# Hive_1_5.net
KiCad netlist of a schematic drawn in EAGLE
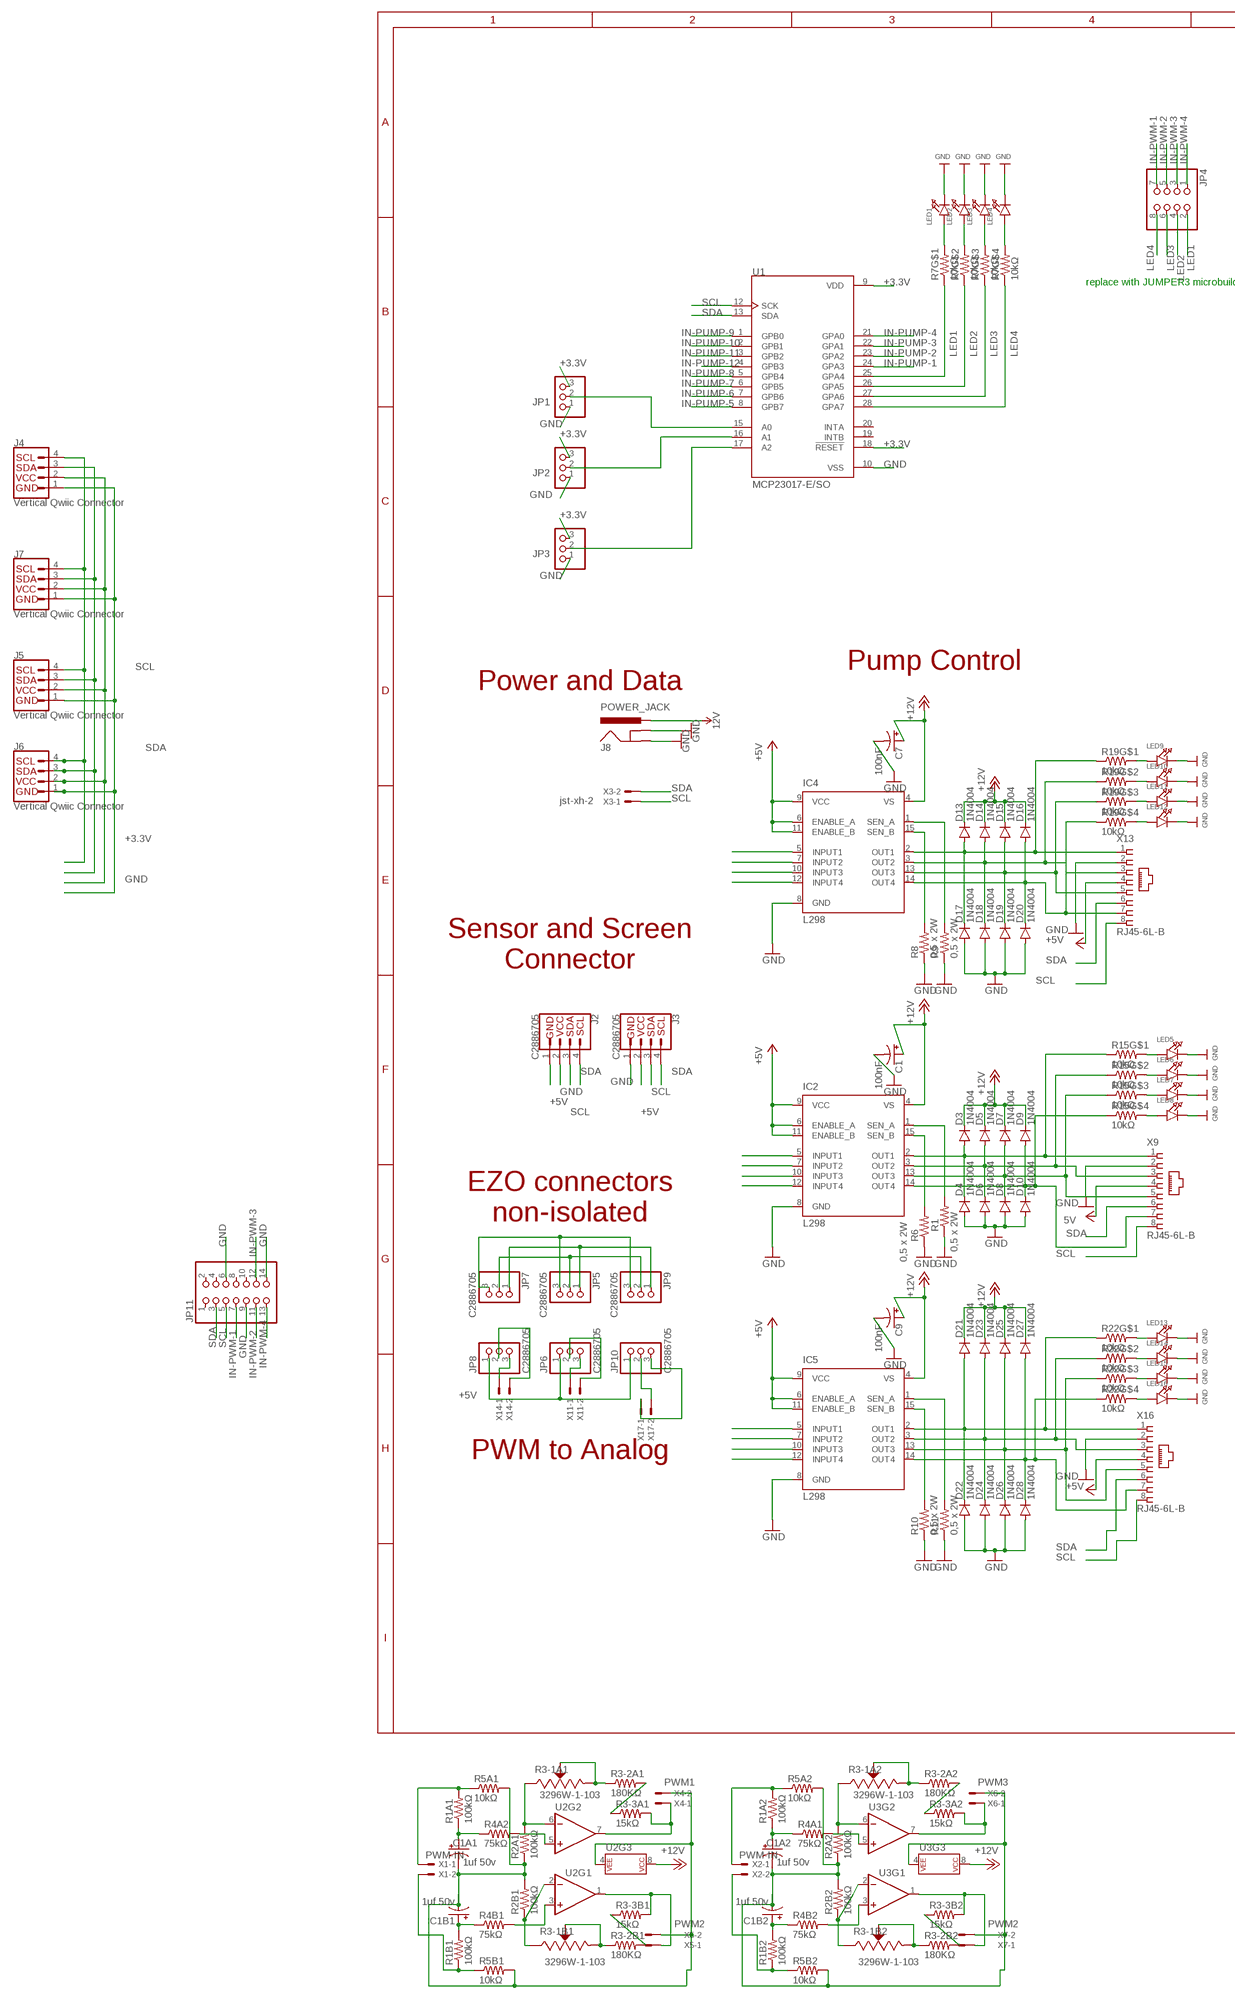
[diagram p0: schematic, sheet 1, part 1 of 2]
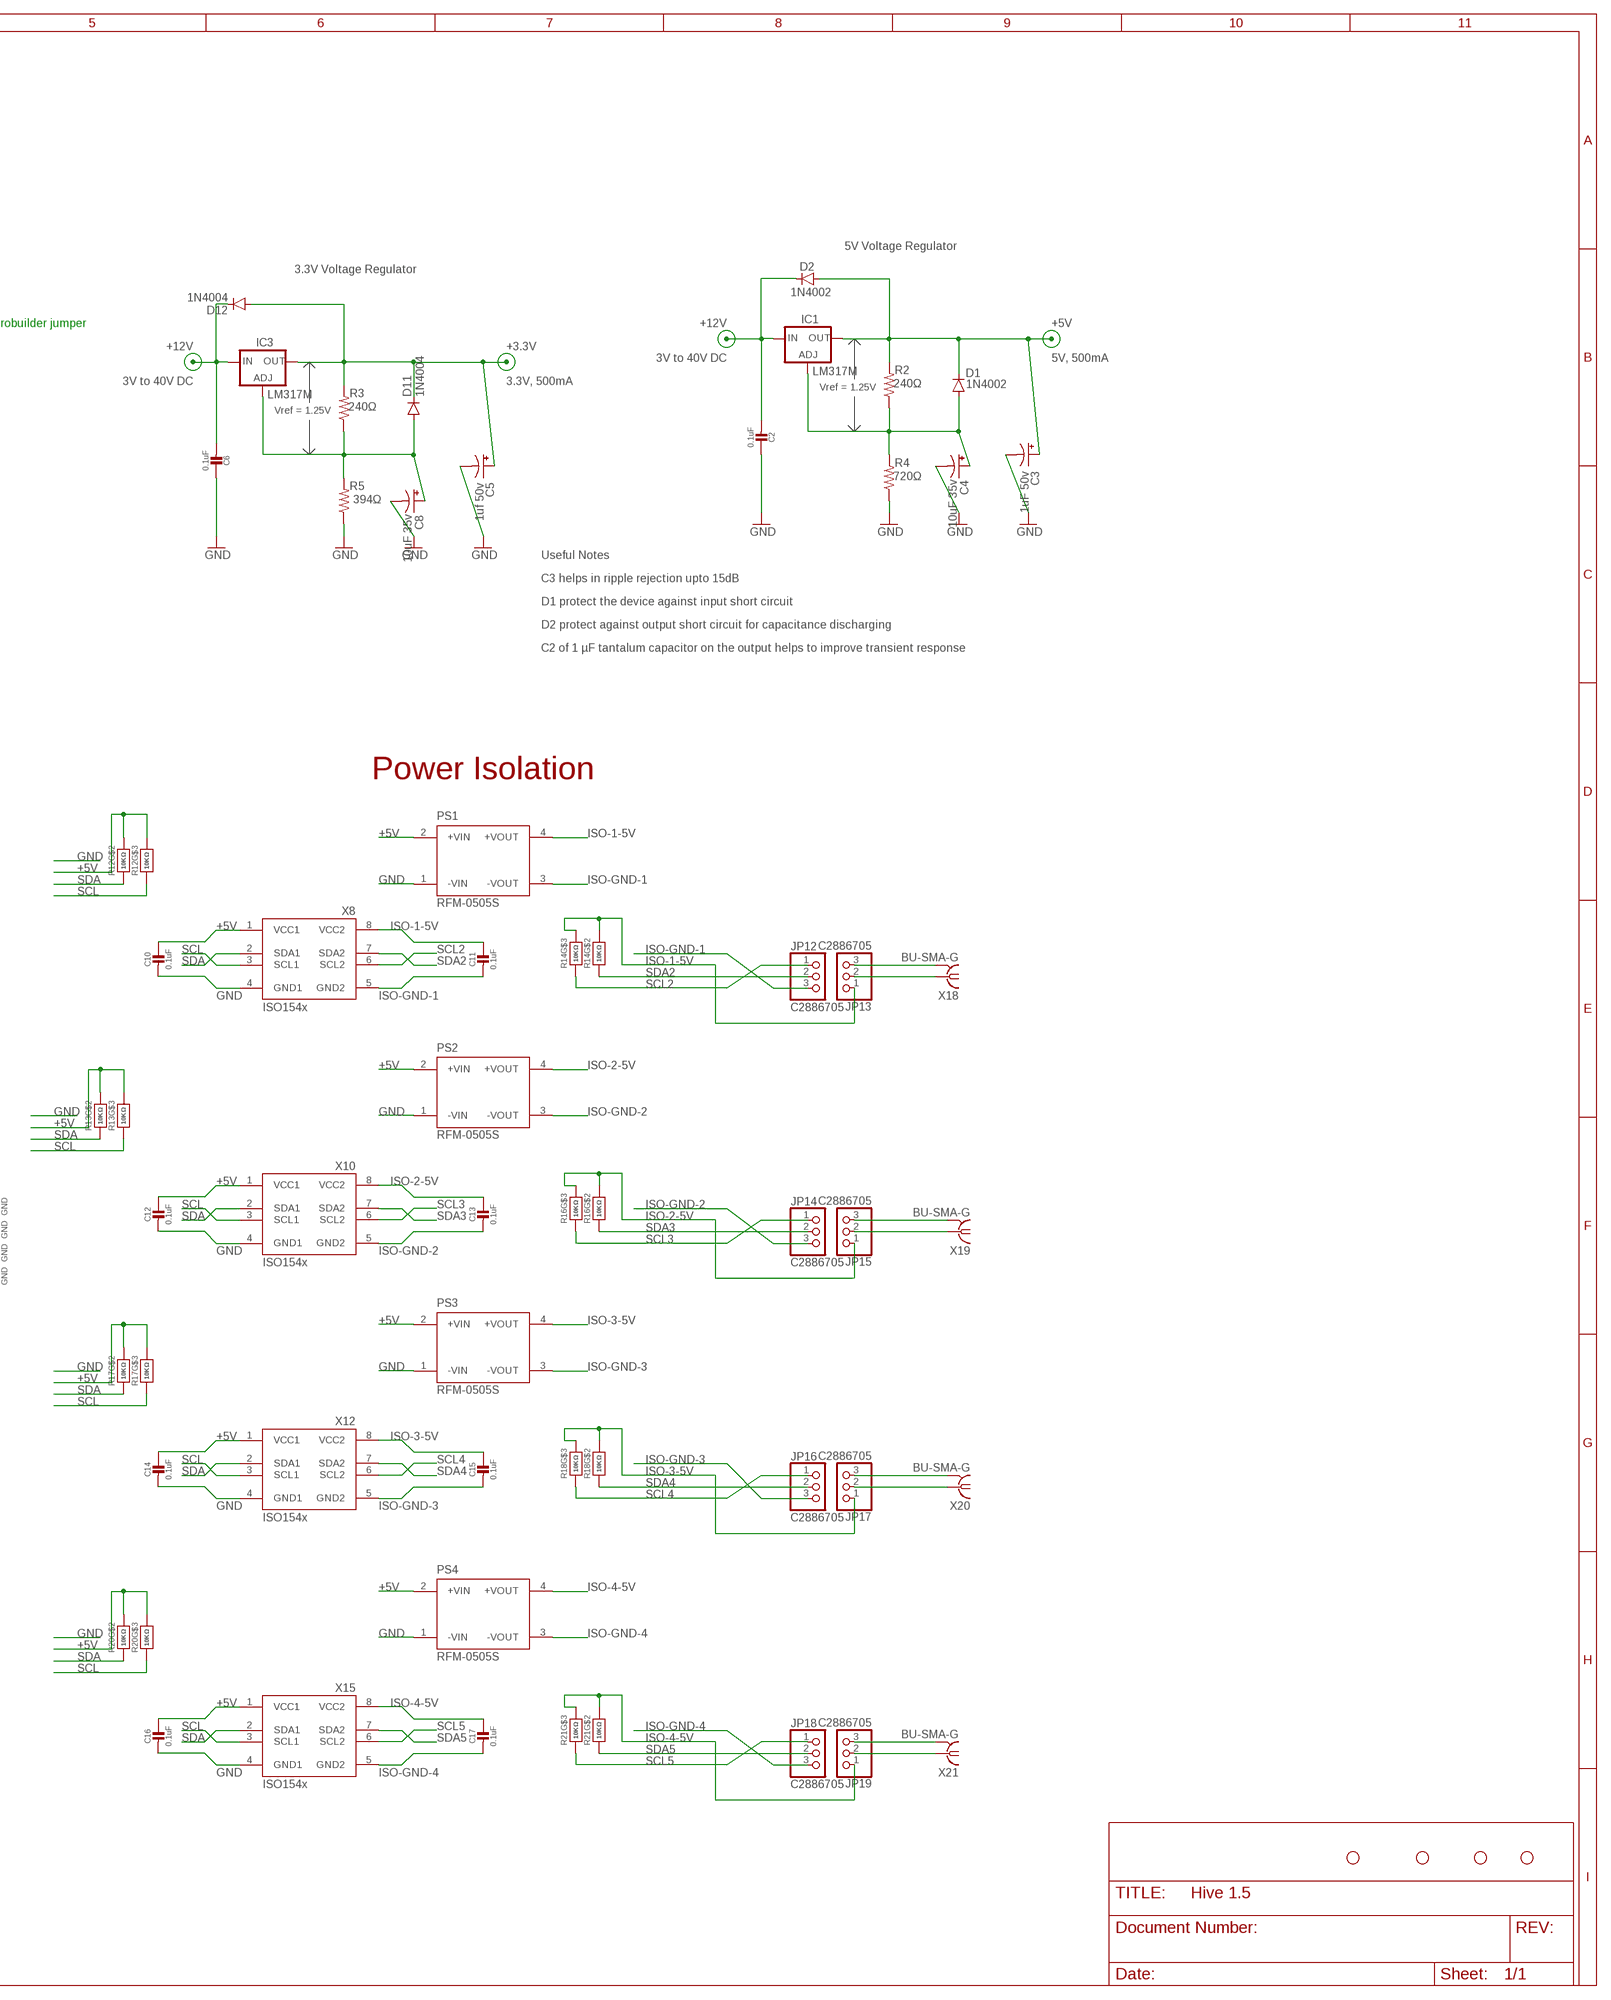
[diagram p1: schematic, sheet 1, part 2 of 2]

(export (version "E")
  (design (tool "Eeschema 10.0.6"))
  (components
    (comp (ref "C1")
      (value "100nF")
      (footprint "eagle-import:UD-4X5,8_NICHICON")
      (libsource (lib "eagle-import") (part "CPOL-USUD-4X5,8"))
    )
    (comp (ref "C1A1")
      (value "1uf 50v")
      (footprint "eagle-import:UD-4X5,8_NICHICON")
      (libsource (lib "eagle-import") (part "CPOL-USUD-4X5,8"))
    )
    (comp (ref "C1A2")
      (value "1uf 50v")
      (footprint "eagle-import:UD-4X5,8_NICHICON")
      (libsource (lib "eagle-import") (part "CPOL-USUD-4X5,8"))
    )
    (comp (ref "C1B1")
      (value "1uf 50v")
      (footprint "eagle-import:UD-4X5,8_NICHICON")
      (libsource (lib "eagle-import") (part "CPOL-USUD-4X5,8"))
    )
    (comp (ref "C1B2")
      (value "1uf 50v")
      (footprint "eagle-import:UD-4X5,8_NICHICON")
      (libsource (lib "eagle-import") (part "CPOL-USUD-4X5,8"))
    )
    (comp (ref "C2")
      (value "0.1uF")
      (footprint "eagle-import:0603-NO")
      (libsource (lib "eagle-import") (part "CAP_CERAMIC0603_NO"))
    )
    (comp (ref "C3")
      (value "1uF 50v")
      (footprint "eagle-import:UD-4X5,8_NICHICON")
      (libsource (lib "eagle-import") (part "CPOL-USUD-4X5,8"))
    )
    (comp (ref "C4")
      (value "10uF 35v")
      (footprint "eagle-import:UD-4X5,8_NICHICON")
      (libsource (lib "eagle-import") (part "CPOL-USUD-4X5,8"))
    )
    (comp (ref "C5")
      (value "1uf 50v")
      (footprint "eagle-import:UD-4X5,8_NICHICON")
      (libsource (lib "eagle-import") (part "CPOL-USUD-4X5,8"))
    )
    (comp (ref "C6")
      (value "0.1uF")
      (footprint "eagle-import:0603-NO")
      (libsource (lib "eagle-import") (part "CAP_CERAMIC0603_NO"))
    )
    (comp (ref "C7")
      (value "100nF")
      (footprint "eagle-import:UD-4X5,8_NICHICON")
      (libsource (lib "eagle-import") (part "CPOL-USUD-4X5,8"))
    )
    (comp (ref "C8")
      (value "10uF 35v")
      (footprint "eagle-import:UD-4X5,8_NICHICON")
      (libsource (lib "eagle-import") (part "CPOL-USUD-4X5,8"))
    )
    (comp (ref "C9")
      (value "100nF")
      (footprint "eagle-import:UD-4X5,8_NICHICON")
      (libsource (lib "eagle-import") (part "CPOL-USUD-4X5,8"))
    )
    (comp (ref "C10")
      (value "0.1uF")
      (footprint "eagle-import:0603-NO")
      (libsource (lib "eagle-import") (part "CAP_CERAMIC0603_NO"))
    )
    (comp (ref "C11")
      (value "0.1uF")
      (footprint "eagle-import:0603-NO")
      (libsource (lib "eagle-import") (part "CAP_CERAMIC0603_NO"))
    )
    (comp (ref "C12")
      (value "0.1uF")
      (footprint "eagle-import:0603-NO")
      (libsource (lib "eagle-import") (part "CAP_CERAMIC0603_NO"))
    )
    (comp (ref "C13")
      (value "0.1uF")
      (footprint "eagle-import:0603-NO")
      (libsource (lib "eagle-import") (part "CAP_CERAMIC0603_NO"))
    )
    (comp (ref "C14")
      (value "0.1uF")
      (footprint "eagle-import:0603-NO")
      (libsource (lib "eagle-import") (part "CAP_CERAMIC0603_NO"))
    )
    (comp (ref "C15")
      (value "0.1uF")
      (footprint "eagle-import:0603-NO")
      (libsource (lib "eagle-import") (part "CAP_CERAMIC0603_NO"))
    )
    (comp (ref "C16")
      (value "0.1uF")
      (footprint "eagle-import:0603-NO")
      (libsource (lib "eagle-import") (part "CAP_CERAMIC0603_NO"))
    )
    (comp (ref "C17")
      (value "0.1uF")
      (footprint "eagle-import:0603-NO")
      (libsource (lib "eagle-import") (part "CAP_CERAMIC0603_NO"))
    )
    (comp (ref "D1")
      (value "1N4002")
      (footprint "eagle-import:DO214BA")
      (libsource (lib "eagle-import") (part "DIODE-DO214BA"))
    )
    (comp (ref "D2")
      (value "1N4002")
      (footprint "eagle-import:DO214BA")
      (libsource (lib "eagle-import") (part "DIODE-DO214BA"))
    )
    (comp (ref "D3")
      (value "1N4004")
      (footprint "eagle-import:DO214BA")
      (libsource (lib "eagle-import") (part "DIODE-DO214BA"))
    )
    (comp (ref "D4")
      (value "1N4004")
      (footprint "eagle-import:DO214BA")
      (libsource (lib "eagle-import") (part "DIODE-DO214BA"))
    )
    (comp (ref "D5")
      (value "1N4004")
      (footprint "eagle-import:DO214BA")
      (libsource (lib "eagle-import") (part "DIODE-DO214BA"))
    )
    (comp (ref "D6")
      (value "1N4004")
      (footprint "eagle-import:DO214BA")
      (libsource (lib "eagle-import") (part "DIODE-DO214BA"))
    )
    (comp (ref "D7")
      (value "1N4004")
      (footprint "eagle-import:DO214BA")
      (libsource (lib "eagle-import") (part "DIODE-DO214BA"))
    )
    (comp (ref "D8")
      (value "1N4004")
      (footprint "eagle-import:DO214BA")
      (libsource (lib "eagle-import") (part "DIODE-DO214BA"))
    )
    (comp (ref "D9")
      (value "1N4004")
      (footprint "eagle-import:DO214BA")
      (libsource (lib "eagle-import") (part "DIODE-DO214BA"))
    )
    (comp (ref "D10")
      (value "1N4004")
      (footprint "eagle-import:DO214BA")
      (libsource (lib "eagle-import") (part "DIODE-DO214BA"))
    )
    (comp (ref "D11")
      (value "1N4004")
      (footprint "eagle-import:DO214BA")
      (libsource (lib "eagle-import") (part "DIODE-DO214BA"))
    )
    (comp (ref "D12")
      (value "1N4004")
      (footprint "eagle-import:DO214BA")
      (libsource (lib "eagle-import") (part "DIODE-DO214BA"))
    )
    (comp (ref "D13")
      (value "1N4004")
      (footprint "eagle-import:DO214BA")
      (libsource (lib "eagle-import") (part "DIODE-DO214BA"))
    )
    (comp (ref "D14")
      (value "1N4004")
      (footprint "eagle-import:DO214BA")
      (libsource (lib "eagle-import") (part "DIODE-DO214BA"))
    )
    (comp (ref "D15")
      (value "1N4004")
      (footprint "eagle-import:DO214BA")
      (libsource (lib "eagle-import") (part "DIODE-DO214BA"))
    )
    (comp (ref "D16")
      (value "1N4004")
      (footprint "eagle-import:DO214BA")
      (libsource (lib "eagle-import") (part "DIODE-DO214BA"))
    )
    (comp (ref "D17")
      (value "1N4004")
      (footprint "eagle-import:DO214BA")
      (libsource (lib "eagle-import") (part "DIODE-DO214BA"))
    )
    (comp (ref "D18")
      (value "1N4004")
      (footprint "eagle-import:DO214BA")
      (libsource (lib "eagle-import") (part "DIODE-DO214BA"))
    )
    (comp (ref "D19")
      (value "1N4004")
      (footprint "eagle-import:DO214BA")
      (libsource (lib "eagle-import") (part "DIODE-DO214BA"))
    )
    (comp (ref "D20")
      (value "1N4004")
      (footprint "eagle-import:DO214BA")
      (libsource (lib "eagle-import") (part "DIODE-DO214BA"))
    )
    (comp (ref "D21")
      (value "1N4004")
      (footprint "eagle-import:DO214BA")
      (libsource (lib "eagle-import") (part "DIODE-DO214BA"))
    )
    (comp (ref "D22")
      (value "1N4004")
      (footprint "eagle-import:DO214BA")
      (libsource (lib "eagle-import") (part "DIODE-DO214BA"))
    )
    (comp (ref "D23")
      (value "1N4004")
      (footprint "eagle-import:DO214BA")
      (libsource (lib "eagle-import") (part "DIODE-DO214BA"))
    )
    (comp (ref "D24")
      (value "1N4004")
      (footprint "eagle-import:DO214BA")
      (libsource (lib "eagle-import") (part "DIODE-DO214BA"))
    )
    (comp (ref "D25")
      (value "1N4004")
      (footprint "eagle-import:DO214BA")
      (libsource (lib "eagle-import") (part "DIODE-DO214BA"))
    )
    (comp (ref "D26")
      (value "1N4004")
      (footprint "eagle-import:DO214BA")
      (libsource (lib "eagle-import") (part "DIODE-DO214BA"))
    )
    (comp (ref "D27")
      (value "1N4004")
      (footprint "eagle-import:DO214BA")
      (libsource (lib "eagle-import") (part "DIODE-DO214BA"))
    )
    (comp (ref "D28")
      (value "1N4004")
      (footprint "eagle-import:DO214BA")
      (libsource (lib "eagle-import") (part "DIODE-DO214BA"))
    )
    (comp (ref "H1")
      (value "STAND-OFF")
      (footprint "eagle-import:STAND-OFF")
      (libsource (lib "eagle-import") (part "STAND-OFF"))
    )
    (comp (ref "H2")
      (value "STAND-OFF")
      (footprint "eagle-import:STAND-OFF")
      (libsource (lib "eagle-import") (part "STAND-OFF"))
    )
    (comp (ref "H3")
      (value "STAND-OFF")
      (footprint "eagle-import:STAND-OFF")
      (libsource (lib "eagle-import") (part "STAND-OFF"))
    )
    (comp (ref "H4")
      (value "STAND-OFF")
      (footprint "eagle-import:STAND-OFF")
      (libsource (lib "eagle-import") (part "STAND-OFF"))
    )
    (comp (ref "IC1")
      (value "LM317MBSTT3")
      (footprint "eagle-import:SOT223")
      (fields (field (name "PARTNUMBER") "LM317M"))
      (libsource (lib "eagle-import") (part "LM317?MBSTT3"))
    )
    (comp (ref "IC2")
      (value "L298")
      (footprint "eagle-import:MULTIWATT-15")
      (fields (field (name "MPN") "L298N"))
      (libsource (lib "eagle-import") (part "L298"))
    )
    (comp (ref "IC3")
      (value "LM317MBSTT3")
      (footprint "eagle-import:SOT223")
      (fields (field (name "PARTNUMBER") "LM317M"))
      (libsource (lib "eagle-import") (part "LM317?MBSTT3"))
    )
    (comp (ref "IC4")
      (value "L298")
      (footprint "eagle-import:MULTIWATT-15")
      (fields (field (name "MPN") "L298N"))
      (libsource (lib "eagle-import") (part "L298"))
    )
    (comp (ref "IC5")
      (value "L298")
      (footprint "eagle-import:MULTIWATT-15")
      (fields (field (name "MPN") "L298N"))
      (libsource (lib "eagle-import") (part "L298"))
    )
    (comp (ref "J2")
      (value "C2886705")
      (footprint "eagle-import:1X04")
      (libsource (lib "eagle-import") (part "I2C_STANDARD"))
    )
    (comp (ref "J3")
      (value "C2886705")
      (footprint "eagle-import:1X04")
      (libsource (lib "eagle-import") (part "I2C_STANDARD"))
    )
    (comp (ref "J4")
      (value "Vertical Qwiic Connector")
      (footprint "eagle-import:JST04_1MM_VERT")
      (libsource (lib "eagle-import") (part "QWIIC_CONNECTOR"))
    )
    (comp (ref "J5")
      (value "Vertical Qwiic Connector")
      (footprint "eagle-import:JST04_1MM_VERT")
      (libsource (lib "eagle-import") (part "QWIIC_CONNECTOR"))
    )
    (comp (ref "J6")
      (value "Vertical Qwiic Connector")
      (footprint "eagle-import:JST04_1MM_VERT")
      (libsource (lib "eagle-import") (part "QWIIC_CONNECTOR"))
    )
    (comp (ref "J7")
      (value "Vertical Qwiic Connector")
      (footprint "eagle-import:JST04_1MM_VERT")
      (libsource (lib "eagle-import") (part "QWIIC_CONNECTOR"))
    )
    (comp (ref "J8")
      (value "POWER_JACK")
      (footprint "eagle-import:POWER_JACK_PTH")
      (libsource (lib "eagle-import") (part "POWER_JACK"))
    )
    (comp (ref "JP1")
      (value "HEADER-1X3ROUND")
      (footprint "eagle-import:1X03_ROUND")
      (libsource (lib "eagle-import") (part "HEADER-1X3ROUND"))
    )
    (comp (ref "JP2")
      (value "HEADER-1X3ROUND")
      (footprint "eagle-import:1X03_ROUND")
      (libsource (lib "eagle-import") (part "HEADER-1X3ROUND"))
    )
    (comp (ref "JP3")
      (value "HEADER-1X3ROUND")
      (footprint "eagle-import:1X03_ROUND")
      (libsource (lib "eagle-import") (part "HEADER-1X3ROUND"))
    )
    (comp (ref "JP4")
      (value "PINHD-2X4")
      (footprint "eagle-import:2X04")
      (libsource (lib "eagle-import") (part "PINHD-2X4"))
    )
    (comp (ref "JP5")
      (value "C2886705")
      (footprint "eagle-import:1X03-CLEANBIG")
      (libsource (lib "eagle-import") (part "PINHD-1X3CB"))
    )
    (comp (ref "JP6")
      (value "C2886705")
      (footprint "eagle-import:1X03-CLEANBIG")
      (libsource (lib "eagle-import") (part "PINHD-1X3CB"))
    )
    (comp (ref "JP7")
      (value "C2886705")
      (footprint "eagle-import:1X03-CLEANBIG")
      (libsource (lib "eagle-import") (part "PINHD-1X3CB"))
    )
    (comp (ref "JP8")
      (value "C2886705")
      (footprint "eagle-import:1X03-CLEANBIG")
      (libsource (lib "eagle-import") (part "PINHD-1X3CB"))
    )
    (comp (ref "JP9")
      (value "C2886705")
      (footprint "eagle-import:1X03-CLEANBIG")
      (libsource (lib "eagle-import") (part "PINHD-1X3CB"))
    )
    (comp (ref "JP10")
      (value "C2886705")
      (footprint "eagle-import:1X03-CLEANBIG")
      (libsource (lib "eagle-import") (part "PINHD-1X3CB"))
    )
    (comp (ref "JP11")
      (value "PINHD-2X7")
      (footprint "eagle-import:2X07")
      (libsource (lib "eagle-import") (part "PINHD-2X7"))
    )
    (comp (ref "JP12")
      (value "C2886705")
      (footprint "eagle-import:1X03-CLEANBIG")
      (libsource (lib "eagle-import") (part "PINHD-1X3CB"))
    )
    (comp (ref "JP13")
      (value "C2886705")
      (footprint "eagle-import:1X03-CLEANBIG")
      (libsource (lib "eagle-import") (part "PINHD-1X3CB"))
    )
    (comp (ref "JP14")
      (value "C2886705")
      (footprint "eagle-import:1X03-CLEANBIG")
      (libsource (lib "eagle-import") (part "PINHD-1X3CB"))
    )
    (comp (ref "JP15")
      (value "C2886705")
      (footprint "eagle-import:1X03-CLEANBIG")
      (libsource (lib "eagle-import") (part "PINHD-1X3CB"))
    )
    (comp (ref "JP16")
      (value "C2886705")
      (footprint "eagle-import:1X03-CLEANBIG")
      (libsource (lib "eagle-import") (part "PINHD-1X3CB"))
    )
    (comp (ref "JP17")
      (value "C2886705")
      (footprint "eagle-import:1X03-CLEANBIG")
      (libsource (lib "eagle-import") (part "PINHD-1X3CB"))
    )
    (comp (ref "JP18")
      (value "C2886705")
      (footprint "eagle-import:1X03-CLEANBIG")
      (libsource (lib "eagle-import") (part "PINHD-1X3CB"))
    )
    (comp (ref "JP19")
      (value "C2886705")
      (footprint "eagle-import:1X03-CLEANBIG")
      (libsource (lib "eagle-import") (part "PINHD-1X3CB"))
    )
    (comp (ref "LED1")
      (value "LED0603")
      (footprint "eagle-import:CHIPLED_0603")
      (libsource (lib "eagle-import") (part "LED0603"))
    )
    (comp (ref "LED2")
      (value "LED0603")
      (footprint "eagle-import:CHIPLED_0603")
      (libsource (lib "eagle-import") (part "LED0603"))
    )
    (comp (ref "LED3")
      (value "LED0603")
      (footprint "eagle-import:CHIPLED_0603")
      (libsource (lib "eagle-import") (part "LED0603"))
    )
    (comp (ref "LED4")
      (value "LED0603")
      (footprint "eagle-import:CHIPLED_0603")
      (libsource (lib "eagle-import") (part "LED0603"))
    )
    (comp (ref "LED5")
      (value "LED0603")
      (footprint "eagle-import:CHIPLED_0603")
      (libsource (lib "eagle-import") (part "LED0603"))
    )
    (comp (ref "LED6")
      (value "LED0603")
      (footprint "eagle-import:CHIPLED_0603")
      (libsource (lib "eagle-import") (part "LED0603"))
    )
    (comp (ref "LED7")
      (value "LED0603")
      (footprint "eagle-import:CHIPLED_0603")
      (libsource (lib "eagle-import") (part "LED0603"))
    )
    (comp (ref "LED8")
      (value "LED0603")
      (footprint "eagle-import:CHIPLED_0603")
      (libsource (lib "eagle-import") (part "LED0603"))
    )
    (comp (ref "LED9")
      (value "LED0603")
      (footprint "eagle-import:CHIPLED_0603")
      (libsource (lib "eagle-import") (part "LED0603"))
    )
    (comp (ref "LED10")
      (value "LED0603")
      (footprint "eagle-import:CHIPLED_0603")
      (libsource (lib "eagle-import") (part "LED0603"))
    )
    (comp (ref "LED11")
      (value "LED0603")
      (footprint "eagle-import:CHIPLED_0603")
      (libsource (lib "eagle-import") (part "LED0603"))
    )
    (comp (ref "LED12")
      (value "LED0603")
      (footprint "eagle-import:CHIPLED_0603")
      (libsource (lib "eagle-import") (part "LED0603"))
    )
    (comp (ref "LED13")
      (value "LED0603")
      (footprint "eagle-import:CHIPLED_0603")
      (libsource (lib "eagle-import") (part "LED0603"))
    )
    (comp (ref "LED14")
      (value "LED0603")
      (footprint "eagle-import:CHIPLED_0603")
      (libsource (lib "eagle-import") (part "LED0603"))
    )
    (comp (ref "LED15")
      (value "LED0603")
      (footprint "eagle-import:CHIPLED_0603")
      (libsource (lib "eagle-import") (part "LED0603"))
    )
    (comp (ref "LED16")
      (value "LED0603")
      (footprint "eagle-import:CHIPLED_0603")
      (libsource (lib "eagle-import") (part "LED0603"))
    )
    (comp (ref "PS1")
      (value "RFM-0505S")
      (footprint "eagle-import:CONV_RFM-0505S")
      (fields (field (name "MF") "Recom Power"))
      (libsource (lib "eagle-import") (part "RFM-0505S"))
    )
    (comp (ref "PS2")
      (value "RFM-0505S")
      (footprint "eagle-import:CONV_RFM-0505S")
      (fields (field (name "MF") "Recom Power"))
      (libsource (lib "eagle-import") (part "RFM-0505S"))
    )
    (comp (ref "PS3")
      (value "RFM-0505S")
      (footprint "eagle-import:CONV_RFM-0505S")
      (fields (field (name "MF") "Recom Power"))
      (libsource (lib "eagle-import") (part "RFM-0505S"))
    )
    (comp (ref "PS4")
      (value "RFM-0505S")
      (footprint "eagle-import:CONV_RFM-0505S")
      (fields (field (name "MF") "Recom Power"))
      (libsource (lib "eagle-import") (part "RFM-0505S"))
    )
    (comp (ref "R1")
      (value "0,5 x 2W")
      (footprint "eagle-import:R2512")
      (libsource (lib "eagle-import") (part "R-US_R2512"))
    )
    (comp (ref "R1A1")
      (value "100kΩ")
      (footprint "eagle-import:M1206")
      (libsource (lib "eagle-import") (part "adafruit_420_R-US_M1206"))
    )
    (comp (ref "R1A2")
      (value "100kΩ")
      (footprint "eagle-import:M1206")
      (libsource (lib "eagle-import") (part "adafruit_420_R-US_M1206"))
    )
    (comp (ref "R1B1")
      (value "100kΩ")
      (footprint "eagle-import:M1206")
      (libsource (lib "eagle-import") (part "adafruit_420_R-US_M1206"))
    )
    (comp (ref "R1B2")
      (value "100kΩ")
      (footprint "eagle-import:M1206")
      (libsource (lib "eagle-import") (part "adafruit_420_R-US_M1206"))
    )
    (comp (ref "R2")
      (value "240Ω")
      (footprint "eagle-import:M0805")
      (libsource (lib "eagle-import") (part "resistor_R-US_M0805"))
    )
    (comp (ref "R2A1")
      (value "100kΩ")
      (footprint "eagle-import:M1206")
      (libsource (lib "eagle-import") (part "adafruit_420_R-US_M1206"))
    )
    (comp (ref "R2A2")
      (value "100kΩ")
      (footprint "eagle-import:M1206")
      (libsource (lib "eagle-import") (part "adafruit_420_R-US_M1206"))
    )
    (comp (ref "R2B1")
      (value "100kΩ")
      (footprint "eagle-import:M1206")
      (libsource (lib "eagle-import") (part "adafruit_420_R-US_M1206"))
    )
    (comp (ref "R2B2")
      (value "100kΩ")
      (footprint "eagle-import:M1206")
      (libsource (lib "eagle-import") (part "adafruit_420_R-US_M1206"))
    )
    (comp (ref "R3")
      (value "240Ω")
      (footprint "eagle-import:M0805")
      (libsource (lib "eagle-import") (part "resistor_R-US_M0805"))
    )
    (comp (ref "R3-1A1")
      (value "3296W-1-103")
      (footprint "eagle-import:TRIM_3296W-1-103")
      (fields (field (name "MF") "Bourns"))
      (libsource (lib "eagle-import") (part "3296W-1-103"))
    )
    (comp (ref "R3-1A2")
      (value "3296W-1-103")
      (footprint "eagle-import:TRIM_3296W-1-103")
      (fields (field (name "MF") "Bourns"))
      (libsource (lib "eagle-import") (part "3296W-1-103"))
    )
    (comp (ref "R3-1B1")
      (value "3296W-1-103")
      (footprint "eagle-import:TRIM_3296W-1-103")
      (fields (field (name "MF") "Bourns"))
      (libsource (lib "eagle-import") (part "3296W-1-103"))
    )
    (comp (ref "R3-1B2")
      (value "3296W-1-103")
      (footprint "eagle-import:TRIM_3296W-1-103")
      (fields (field (name "MF") "Bourns"))
      (libsource (lib "eagle-import") (part "3296W-1-103"))
    )
    (comp (ref "R3-2A1")
      (value "180KΩ")
      (footprint "eagle-import:M1206")
      (libsource (lib "eagle-import") (part "adafruit_420_R-US_M1206"))
    )
    (comp (ref "R3-2A2")
      (value "180KΩ")
      (footprint "eagle-import:M1206")
      (libsource (lib "eagle-import") (part "adafruit_420_R-US_M1206"))
    )
    (comp (ref "R3-2B1")
      (value "180KΩ")
      (footprint "eagle-import:M1206")
      (libsource (lib "eagle-import") (part "adafruit_420_R-US_M1206"))
    )
    (comp (ref "R3-2B2")
      (value "180KΩ")
      (footprint "eagle-import:M1206")
      (libsource (lib "eagle-import") (part "adafruit_420_R-US_M1206"))
    )
    (comp (ref "R3-3A1")
      (value "15kΩ")
      (footprint "eagle-import:M1206")
      (libsource (lib "eagle-import") (part "adafruit_420_R-US_M1206"))
    )
    (comp (ref "R3-3A2")
      (value "15kΩ")
      (footprint "eagle-import:M1206")
      (libsource (lib "eagle-import") (part "adafruit_420_R-US_M1206"))
    )
    (comp (ref "R3-3B1")
      (value "15kΩ")
      (footprint "eagle-import:M1206")
      (libsource (lib "eagle-import") (part "adafruit_420_R-US_M1206"))
    )
    (comp (ref "R3-3B2")
      (value "15kΩ")
      (footprint "eagle-import:M1206")
      (libsource (lib "eagle-import") (part "adafruit_420_R-US_M1206"))
    )
    (comp (ref "R4")
      (value "720Ω")
      (footprint "eagle-import:M0805")
      (libsource (lib "eagle-import") (part "resistor_R-US_M0805"))
    )
    (comp (ref "R4A1")
      (value "75kΩ")
      (footprint "eagle-import:M1206")
      (libsource (lib "eagle-import") (part "adafruit_420_R-US_M1206"))
    )
    (comp (ref "R4A2")
      (value "75kΩ")
      (footprint "eagle-import:M1206")
      (libsource (lib "eagle-import") (part "adafruit_420_R-US_M1206"))
    )
    (comp (ref "R4B1")
      (value "75kΩ")
      (footprint "eagle-import:M1206")
      (libsource (lib "eagle-import") (part "adafruit_420_R-US_M1206"))
    )
    (comp (ref "R4B2")
      (value "75kΩ")
      (footprint "eagle-import:M1206")
      (libsource (lib "eagle-import") (part "adafruit_420_R-US_M1206"))
    )
    (comp (ref "R5")
      (value "394Ω")
      (footprint "eagle-import:M0805")
      (libsource (lib "eagle-import") (part "resistor_R-US_M0805"))
    )
    (comp (ref "R5A1")
      (value "10kΩ")
      (footprint "eagle-import:M1206")
      (libsource (lib "eagle-import") (part "adafruit_420_R-US_M1206"))
    )
    (comp (ref "R5A2")
      (value "10kΩ")
      (footprint "eagle-import:M1206")
      (libsource (lib "eagle-import") (part "adafruit_420_R-US_M1206"))
    )
    (comp (ref "R5B1")
      (value "10kΩ")
      (footprint "eagle-import:M1206")
      (libsource (lib "eagle-import") (part "adafruit_420_R-US_M1206"))
    )
    (comp (ref "R5B2")
      (value "10kΩ")
      (footprint "eagle-import:M1206")
      (libsource (lib "eagle-import") (part "adafruit_420_R-US_M1206"))
    )
    (comp (ref "R6")
      (value "0,5 x 2W")
      (footprint "eagle-import:R2512")
      (libsource (lib "eagle-import") (part "R-US_R2512"))
    )
    (comp (ref "R7")
      (value "10kΩ")
      (footprint "eagle-import:RESPACK_4X0603")
      (libsource (lib "eagle-import") (part "RESISTOR_4PACK_US"))
    )
    (comp (ref "R8")
      (value "0,5 x 2W")
      (footprint "eagle-import:R2512")
      (libsource (lib "eagle-import") (part "R-US_R2512"))
    )
    (comp (ref "R9")
      (value "0,5 x 2W")
      (footprint "eagle-import:R2512")
      (libsource (lib "eagle-import") (part "R-US_R2512"))
    )
    (comp (ref "R10")
      (value "0,5 x 2W")
      (footprint "eagle-import:R2512")
      (libsource (lib "eagle-import") (part "R-US_R2512"))
    )
    (comp (ref "R11")
      (value "0,5 x 2W")
      (footprint "eagle-import:R2512")
      (libsource (lib "eagle-import") (part "R-US_R2512"))
    )
    (comp (ref "R12")
      (value "10KΩ")
      (footprint "eagle-import:RESPACK_4X0603")
      (libsource (lib "eagle-import") (part "RESISTOR_4PACK"))
    )
    (comp (ref "R13")
      (value "10KΩ")
      (footprint "eagle-import:RESPACK_4X0603")
      (libsource (lib "eagle-import") (part "RESISTOR_4PACK"))
    )
    (comp (ref "R14")
      (value "10KΩ")
      (footprint "eagle-import:RESPACK_4X0603")
      (libsource (lib "eagle-import") (part "RESISTOR_4PACK"))
    )
    (comp (ref "R15")
      (value "10kΩ")
      (footprint "eagle-import:RESPACK_4X0603")
      (libsource (lib "eagle-import") (part "RESISTOR_4PACK_US"))
    )
    (comp (ref "R16")
      (value "10KΩ")
      (footprint "eagle-import:RESPACK_4X0603")
      (libsource (lib "eagle-import") (part "RESISTOR_4PACK"))
    )
    (comp (ref "R17")
      (value "10KΩ")
      (footprint "eagle-import:RESPACK_4X0603")
      (libsource (lib "eagle-import") (part "RESISTOR_4PACK"))
    )
    (comp (ref "R18")
      (value "10KΩ")
      (footprint "eagle-import:RESPACK_4X0603")
      (libsource (lib "eagle-import") (part "RESISTOR_4PACK"))
    )
    (comp (ref "R19")
      (value "10kΩ")
      (footprint "eagle-import:RESPACK_4X0603")
      (libsource (lib "eagle-import") (part "RESISTOR_4PACK_US"))
    )
    (comp (ref "R20")
      (value "10KΩ")
      (footprint "eagle-import:RESPACK_4X0603")
      (libsource (lib "eagle-import") (part "RESISTOR_4PACK"))
    )
    (comp (ref "R21")
      (value "10KΩ")
      (footprint "eagle-import:RESPACK_4X0603")
      (libsource (lib "eagle-import") (part "RESISTOR_4PACK"))
    )
    (comp (ref "R22")
      (value "10kΩ")
      (footprint "eagle-import:RESPACK_4X0603")
      (libsource (lib "eagle-import") (part "RESISTOR_4PACK_US"))
    )
    (comp (ref "U1")
      (value "MCP23017-E/SO")
      (footprint "eagle-import:SOIC127P1030X265-28N")
      (fields (field (name "MF") "Microchip"))
      (libsource (lib "eagle-import") (part "MCP23017-E/SO"))
    )
    (comp (ref "U2")
      (value "LM358")
      (footprint "eagle-import:SO08")
      (libsource (lib "eagle-import") (part "LM358SO08"))
    )
    (comp (ref "U3")
      (value "LM358")
      (footprint "eagle-import:SO08")
      (libsource (lib "eagle-import") (part "LM358SO08"))
    )
    (comp (ref "X1")
      (value "PWM-IN")
      (footprint "eagle-import:JST-XH-02-PACKAGE-LONG-PAD")
      (libsource (lib "eagle-import") (part "JST-XH-02-PIN-LONG-PAD"))
    )
    (comp (ref "X2")
      (value "PWM-IN")
      (footprint "eagle-import:JST-XH-02-PACKAGE-LONG-PAD")
      (libsource (lib "eagle-import") (part "JST-XH-02-PIN-LONG-PAD"))
    )
    (comp (ref "X3")
      (value "jst-xh-2")
      (footprint "eagle-import:JST-XH-02-PACKAGE-LONG-PAD")
      (libsource (lib "eagle-import") (part "JST-XH-02-PIN-LONG-PAD"))
    )
    (comp (ref "X4")
      (value "PWM1")
      (footprint "eagle-import:JST-XH-02-PACKAGE-LONG-PAD")
      (libsource (lib "eagle-import") (part "JST-XH-02-PIN-LONG-PAD"))
    )
    (comp (ref "X5")
      (value "PWM2")
      (footprint "eagle-import:JST-XH-02-PACKAGE-LONG-PAD")
      (libsource (lib "eagle-import") (part "JST-XH-02-PIN-LONG-PAD"))
    )
    (comp (ref "X6")
      (value "PWM3")
      (footprint "eagle-import:JST-XH-02-PACKAGE-LONG-PAD")
      (libsource (lib "eagle-import") (part "JST-XH-02-PIN-LONG-PAD"))
    )
    (comp (ref "X7")
      (value "PWM2")
      (footprint "eagle-import:JST-XH-02-PACKAGE-LONG-PAD")
      (libsource (lib "eagle-import") (part "JST-XH-02-PIN-LONG-PAD"))
    )
    (comp (ref "X8")
      (value "ISO154X")
      (footprint "eagle-import:SOIC8_150MIL")
      (libsource (lib "eagle-import") (part "ISO154X"))
    )
    (comp (ref "X9")
      (value "RJ45-6L-B")
      (footprint "eagle-import:RJ45-NO-SHIELD")
      (libsource (lib "eagle-import") (part "RJ45-6L-B"))
    )
    (comp (ref "X10")
      (value "ISO154X")
      (footprint "eagle-import:SOIC8_150MIL")
      (libsource (lib "eagle-import") (part "ISO154X"))
    )
    (comp (ref "X11")
      (value "jst-xh-2")
      (footprint "eagle-import:JST-XH-02-PACKAGE-LONG-PAD")
      (libsource (lib "eagle-import") (part "JST-XH-02-PIN-LONG-PAD"))
    )
    (comp (ref "X12")
      (value "ISO154X")
      (footprint "eagle-import:SOIC8_150MIL")
      (libsource (lib "eagle-import") (part "ISO154X"))
    )
    (comp (ref "X13")
      (value "RJ45-6L-B")
      (footprint "eagle-import:RJ45-NO-SHIELD")
      (libsource (lib "eagle-import") (part "RJ45-6L-B"))
    )
    (comp (ref "X14")
      (value "jst-xh-2")
      (footprint "eagle-import:JST-XH-02-PACKAGE-LONG-PAD")
      (libsource (lib "eagle-import") (part "JST-XH-02-PIN-LONG-PAD"))
    )
    (comp (ref "X15")
      (value "ISO154X")
      (footprint "eagle-import:SOIC8_150MIL")
      (libsource (lib "eagle-import") (part "ISO154X"))
    )
    (comp (ref "X16")
      (value "RJ45-6L-B")
      (footprint "eagle-import:RJ45-NO-SHIELD")
      (libsource (lib "eagle-import") (part "RJ45-6L-B"))
    )
    (comp (ref "X17")
      (value "jst-xh-2")
      (footprint "eagle-import:JST-XH-02-PACKAGE-LONG-PAD")
      (libsource (lib "eagle-import") (part "JST-XH-02-PIN-LONG-PAD"))
    )
    (comp (ref "X18")
      (value "BU-SMA-G")
      (footprint "eagle-import:BU-SMA-G")
      (libsource (lib "eagle-import") (part "BU-SMA-G"))
    )
    (comp (ref "X19")
      (value "BU-SMA-G")
      (footprint "eagle-import:BU-SMA-G")
      (libsource (lib "eagle-import") (part "BU-SMA-G"))
    )
    (comp (ref "X20")
      (value "BU-SMA-G")
      (footprint "eagle-import:BU-SMA-G")
      (libsource (lib "eagle-import") (part "BU-SMA-G"))
    )
    (comp (ref "X21")
      (value "BU-SMA-G")
      (footprint "eagle-import:BU-SMA-G")
      (libsource (lib "eagle-import") (part "BU-SMA-G"))
    )
  )
  (nets
    (net (code "1") (name "+3V3") (class "Default")
      (node (ref "C10") (pin "1") (pinfunction "1_1") (pintype "passive"))
      (node (ref "C12") (pin "1") (pinfunction "1_1") (pintype "passive"))
      (node (ref "C14") (pin "1") (pinfunction "1_1") (pintype "passive"))
      (node (ref "C16") (pin "1") (pinfunction "1_1") (pintype "passive"))
      (node (ref "C3") (pin "+") (pinfunction "+_+") (pintype "passive"))
      (node (ref "D1") (pin "C") (pinfunction "C_C") (pintype "passive"))
      (node (ref "D2") (pin "A") (pinfunction "A_A") (pintype "passive"))
      (node (ref "IC1") (pin "4") (pinfunction "OUT_4") (pintype "passive"))
      (node (ref "IC2") (pin "11") (pinfunction "ENABLE_B_11") (pintype "input"))
      (node (ref "IC2") (pin "6") (pinfunction "ENABLE_A_6") (pintype "input"))
      (node (ref "IC2") (pin "9") (pinfunction "VCC_9") (pintype "power_in"))
      (node (ref "IC4") (pin "11") (pinfunction "ENABLE_B_11") (pintype "input"))
      (node (ref "IC4") (pin "6") (pinfunction "ENABLE_A_6") (pintype "input"))
      (node (ref "IC4") (pin "9") (pinfunction "VCC_9") (pintype "power_in"))
      (node (ref "IC5") (pin "11") (pinfunction "ENABLE_B_11") (pintype "input"))
      (node (ref "IC5") (pin "6") (pinfunction "ENABLE_A_6") (pintype "input"))
      (node (ref "IC5") (pin "9") (pinfunction "VCC_9") (pintype "power_in"))
      (node (ref "J2") (pin "1") (pinfunction "1_1") (pintype "power_in"))
      (node (ref "J3") (pin "2") (pinfunction "2_2") (pintype "power_in"))
      (node (ref "JP10") (pin "1") (pinfunction "1_1") (pintype "passive"))
      (node (ref "JP6") (pin "1") (pinfunction "1_1") (pintype "passive"))
      (node (ref "JP8") (pin "1") (pinfunction "1_1") (pintype "passive"))
      (node (ref "PS1") (pin "2") (pinfunction "+VIN_2") (pintype "input"))
      (node (ref "PS2") (pin "2") (pinfunction "+VIN_2") (pintype "input"))
      (node (ref "PS3") (pin "2") (pinfunction "+VIN_2") (pintype "input"))
      (node (ref "PS4") (pin "2") (pinfunction "+VIN_2") (pintype "input"))
      (node (ref "R12") (pin "6") (pinfunction "2_6") (pintype "passive"))
      (node (ref "R12") (pin "7") (pinfunction "2_7") (pintype "passive"))
      (node (ref "R13") (pin "6") (pinfunction "2_6") (pintype "passive"))
      (node (ref "R13") (pin "7") (pinfunction "2_7") (pintype "passive"))
      (node (ref "R17") (pin "6") (pinfunction "2_6") (pintype "passive"))
      (node (ref "R17") (pin "7") (pinfunction "2_7") (pintype "passive"))
      (node (ref "R2") (pin "2") (pinfunction "2_2") (pintype "passive"))
      (node (ref "R20") (pin "6") (pinfunction "2_6") (pintype "passive"))
      (node (ref "R20") (pin "7") (pinfunction "2_7") (pintype "passive"))
      (node (ref "X10") (pin "1") (pinfunction "VCC1_1") (pintype "power_in"))
      (node (ref "X12") (pin "1") (pinfunction "VCC1_1") (pintype "power_in"))
      (node (ref "X13") (pin "4") (pinfunction "4_4") (pintype "passive"))
      (node (ref "X15") (pin "1") (pinfunction "VCC1_1") (pintype "power_in"))
      (node (ref "X16") (pin "4") (pinfunction "4_4") (pintype "passive"))
      (node (ref "X8") (pin "1") (pinfunction "VCC1_1") (pintype "power_in"))
      (node (ref "X9") (pin "4") (pinfunction "4_4") (pintype "passive"))
    )
    (net (code "2") (name "+12V") (class "Default")
      (node (ref "C1") (pin "+") (pinfunction "+_+") (pintype "passive"))
      (node (ref "C2") (pin "2") (pinfunction "2_2") (pintype "passive"))
      (node (ref "C6") (pin "2") (pinfunction "2_2") (pintype "passive"))
      (node (ref "C7") (pin "+") (pinfunction "+_+") (pintype "passive"))
      (node (ref "C9") (pin "+") (pinfunction "+_+") (pintype "passive"))
      (node (ref "D12") (pin "C") (pinfunction "C_C") (pintype "passive"))
      (node (ref "D13") (pin "C") (pinfunction "C_C") (pintype "passive"))
      (node (ref "D14") (pin "C") (pinfunction "C_C") (pintype "passive"))
      (node (ref "D15") (pin "C") (pinfunction "C_C") (pintype "passive"))
      (node (ref "D16") (pin "C") (pinfunction "C_C") (pintype "passive"))
      (node (ref "D2") (pin "C") (pinfunction "C_C") (pintype "passive"))
      (node (ref "D21") (pin "C") (pinfunction "C_C") (pintype "passive"))
      (node (ref "D23") (pin "C") (pinfunction "C_C") (pintype "passive"))
      (node (ref "D25") (pin "C") (pinfunction "C_C") (pintype "passive"))
      (node (ref "D27") (pin "C") (pinfunction "C_C") (pintype "passive"))
      (node (ref "D3") (pin "C") (pinfunction "C_C") (pintype "passive"))
      (node (ref "D5") (pin "C") (pinfunction "C_C") (pintype "passive"))
      (node (ref "D7") (pin "C") (pinfunction "C_C") (pintype "passive"))
      (node (ref "D9") (pin "C") (pinfunction "C_C") (pintype "passive"))
      (node (ref "IC1") (pin "3") (pinfunction "IN_3") (pintype "input"))
      (node (ref "IC2") (pin "4") (pinfunction "VS_4") (pintype "power_in"))
      (node (ref "IC3") (pin "3") (pinfunction "IN_3") (pintype "input"))
      (node (ref "IC4") (pin "4") (pinfunction "VS_4") (pintype "power_in"))
      (node (ref "IC5") (pin "4") (pinfunction "VS_4") (pintype "power_in"))
      (node (ref "U2") (pin "8") (pinfunction "P$V+_8") (pintype "bidirectional"))
      (node (ref "U3") (pin "8") (pinfunction "P$V+_8") (pintype "bidirectional"))
    )
    (net (code "3") (name "/+3.3V") (class "Default")
      (node (ref "C5") (pin "+") (pinfunction "+_+") (pintype "passive"))
      (node (ref "D11") (pin "C") (pinfunction "C_C") (pintype "passive"))
      (node (ref "D12") (pin "A") (pinfunction "A_A") (pintype "passive"))
      (node (ref "IC3") (pin "4") (pinfunction "OUT_4") (pintype "passive"))
      (node (ref "J4") (pin "2") (pinfunction "2_2") (pintype "power_in"))
      (node (ref "J5") (pin "2") (pinfunction "2_2") (pintype "power_in"))
      (node (ref "J6") (pin "2") (pinfunction "2_2") (pintype "power_in"))
      (node (ref "J7") (pin "2") (pinfunction "2_2") (pintype "power_in"))
      (node (ref "JP1") (pin "3") (pinfunction "3_3") (pintype "passive"))
      (node (ref "JP2") (pin "3") (pinfunction "3_3") (pintype "passive"))
      (node (ref "JP3") (pin "3") (pinfunction "3_3") (pintype "passive"))
      (node (ref "R3") (pin "2") (pinfunction "2_2") (pintype "passive"))
      (node (ref "U1") (pin "18") (pinfunction "~{RESET}_18") (pintype "output"))
      (node (ref "U1") (pin "9") (pinfunction "VDD_9") (pintype "power_in"))
    )
    (net (code "4") (name "/IN-PUMP-1") (class "Default")
      (node (ref "IC2") (pin "5") (pinfunction "INPUT1_5") (pintype "input"))
      (node (ref "U1") (pin "24") (pinfunction "GPA3_24") (pintype "bidirectional"))
    )
    (net (code "5") (name "/IN-PUMP-2") (class "Default")
      (node (ref "IC2") (pin "7") (pinfunction "INPUT2_7") (pintype "input"))
      (node (ref "U1") (pin "23") (pinfunction "GPA2_23") (pintype "bidirectional"))
    )
    (net (code "6") (name "/IN-PUMP-3") (class "Default")
      (node (ref "IC2") (pin "10") (pinfunction "INPUT3_10") (pintype "input"))
      (node (ref "U1") (pin "22") (pinfunction "GPA1_22") (pintype "bidirectional"))
    )
    (net (code "7") (name "/IN-PUMP-4") (class "Default")
      (node (ref "IC2") (pin "12") (pinfunction "INPUT4_12") (pintype "input"))
      (node (ref "U1") (pin "21") (pinfunction "GPA0_21") (pintype "bidirectional"))
    )
    (net (code "8") (name "/IN-PUMP-5") (class "Default")
      (node (ref "IC4") (pin "5") (pinfunction "INPUT1_5") (pintype "input"))
      (node (ref "U1") (pin "8") (pinfunction "GPB7_8") (pintype "bidirectional"))
    )
    (net (code "9") (name "/IN-PUMP-6") (class "Default")
      (node (ref "IC4") (pin "7") (pinfunction "INPUT2_7") (pintype "input"))
      (node (ref "U1") (pin "7") (pinfunction "GPB6_7") (pintype "bidirectional"))
    )
    (net (code "10") (name "/IN-PUMP-7") (class "Default")
      (node (ref "IC4") (pin "10") (pinfunction "INPUT3_10") (pintype "input"))
      (node (ref "U1") (pin "6") (pinfunction "GPB5_6") (pintype "bidirectional"))
    )
    (net (code "11") (name "/IN-PUMP-8") (class "Default")
      (node (ref "IC4") (pin "12") (pinfunction "INPUT4_12") (pintype "input"))
      (node (ref "U1") (pin "5") (pinfunction "GPB4_5") (pintype "bidirectional"))
    )
    (net (code "12") (name "/IN-PUMP-9") (class "Default")
      (node (ref "IC5") (pin "5") (pinfunction "INPUT1_5") (pintype "input"))
      (node (ref "U1") (pin "1") (pinfunction "GPB0_1") (pintype "bidirectional"))
    )
    (net (code "13") (name "/IN-PUMP-10") (class "Default")
      (node (ref "IC5") (pin "7") (pinfunction "INPUT2_7") (pintype "input"))
      (node (ref "U1") (pin "2") (pinfunction "GPB1_2") (pintype "bidirectional"))
    )
    (net (code "14") (name "/IN-PUMP-11") (class "Default")
      (node (ref "IC5") (pin "10") (pinfunction "INPUT3_10") (pintype "input"))
      (node (ref "U1") (pin "3") (pinfunction "GPB2_3") (pintype "bidirectional"))
    )
    (net (code "15") (name "/IN-PUMP-12") (class "Default")
      (node (ref "IC5") (pin "12") (pinfunction "INPUT4_12") (pintype "input"))
      (node (ref "U1") (pin "4") (pinfunction "GPB3_4") (pintype "bidirectional"))
    )
    (net (code "16") (name "/IN-PWM-1") (class "Default")
      (node (ref "JP11") (pin "7") (pinfunction "7_7") (pintype "passive"))
      (node (ref "JP4") (pin "7") (pinfunction "7_7") (pintype "passive"))
      (node (ref "R1A1") (pin "2") (pinfunction "2_2") (pintype "passive"))
      (node (ref "R5A1") (pin "1") (pinfunction "1_1") (pintype "passive"))
      (node (ref "X1") (pin "1") (pinfunction "S_1") (pintype "passive"))
    )
    (net (code "17") (name "/IN-PWM-2") (class "Default")
      (node (ref "JP11") (pin "11") (pinfunction "11_11") (pintype "passive"))
      (node (ref "JP4") (pin "5") (pinfunction "5_5") (pintype "passive"))
      (node (ref "R1B1") (pin "1") (pinfunction "1_1") (pintype "passive"))
      (node (ref "R5B1") (pin "1") (pinfunction "1_1") (pintype "passive"))
      (node (ref "X1") (pin "2") (pinfunction "S_2") (pintype "passive"))
    )
    (net (code "18") (name "/IN-PWM-3") (class "Default")
      (node (ref "JP11") (pin "12") (pinfunction "12_12") (pintype "passive"))
      (node (ref "JP4") (pin "3") (pinfunction "3_3") (pintype "passive"))
      (node (ref "R1A2") (pin "2") (pinfunction "2_2") (pintype "passive"))
      (node (ref "R5A2") (pin "1") (pinfunction "1_1") (pintype "passive"))
      (node (ref "X2") (pin "1") (pinfunction "S_1") (pintype "passive"))
    )
    (net (code "19") (name "/IN-PWM-4") (class "Default")
      (node (ref "JP11") (pin "13") (pinfunction "13_13") (pintype "passive"))
      (node (ref "JP4") (pin "1") (pinfunction "1_1") (pintype "passive"))
      (node (ref "R1B2") (pin "1") (pinfunction "1_1") (pintype "passive"))
      (node (ref "R5B2") (pin "1") (pinfunction "1_1") (pintype "passive"))
      (node (ref "X2") (pin "2") (pinfunction "S_2") (pintype "passive"))
    )
    (net (code "20") (name "/ISO-1-5V") (class "Default")
      (node (ref "C11") (pin "1") (pinfunction "1_1") (pintype "passive"))
      (node (ref "JP13") (pin "1") (pinfunction "1_1") (pintype "passive"))
      (node (ref "PS1") (pin "4") (pinfunction "+VOUT_4") (pintype "output"))
      (node (ref "R14") (pin "6") (pinfunction "2_6") (pintype "passive"))
      (node (ref "R14") (pin "7") (pinfunction "2_7") (pintype "passive"))
      (node (ref "X8") (pin "8") (pinfunction "VCC2_8") (pintype "power_in"))
    )
    (net (code "21") (name "/ISO-2-5V") (class "Default")
      (node (ref "C13") (pin "1") (pinfunction "1_1") (pintype "passive"))
      (node (ref "JP15") (pin "1") (pinfunction "1_1") (pintype "passive"))
      (node (ref "PS2") (pin "4") (pinfunction "+VOUT_4") (pintype "output"))
      (node (ref "R16") (pin "6") (pinfunction "2_6") (pintype "passive"))
      (node (ref "R16") (pin "7") (pinfunction "2_7") (pintype "passive"))
      (node (ref "X10") (pin "8") (pinfunction "VCC2_8") (pintype "power_in"))
    )
    (net (code "22") (name "/ISO-3-5V") (class "Default")
      (node (ref "C15") (pin "1") (pinfunction "1_1") (pintype "passive"))
      (node (ref "JP17") (pin "1") (pinfunction "1_1") (pintype "passive"))
      (node (ref "PS3") (pin "4") (pinfunction "+VOUT_4") (pintype "output"))
      (node (ref "R18") (pin "6") (pinfunction "2_6") (pintype "passive"))
      (node (ref "R18") (pin "7") (pinfunction "2_7") (pintype "passive"))
      (node (ref "X12") (pin "8") (pinfunction "VCC2_8") (pintype "power_in"))
    )
    (net (code "23") (name "/ISO-4-5V") (class "Default")
      (node (ref "C17") (pin "1") (pinfunction "1_1") (pintype "passive"))
      (node (ref "JP19") (pin "1") (pinfunction "1_1") (pintype "passive"))
      (node (ref "PS4") (pin "4") (pinfunction "+VOUT_4") (pintype "output"))
      (node (ref "R21") (pin "6") (pinfunction "2_6") (pintype "passive"))
      (node (ref "R21") (pin "7") (pinfunction "2_7") (pintype "passive"))
      (node (ref "X15") (pin "8") (pinfunction "VCC2_8") (pintype "power_in"))
    )
    (net (code "24") (name "/ISO-GND-1") (class "Default")
      (node (ref "C11") (pin "2") (pinfunction "2_2") (pintype "passive"))
      (node (ref "JP12") (pin "3") (pinfunction "3_3") (pintype "passive"))
      (node (ref "PS1") (pin "3") (pinfunction "-VOUT_3") (pintype "output"))
      (node (ref "X8") (pin "5") (pinfunction "GND2_5") (pintype "power_in"))
    )
    (net (code "25") (name "/ISO-GND-2") (class "Default")
      (node (ref "C13") (pin "2") (pinfunction "2_2") (pintype "passive"))
      (node (ref "JP14") (pin "3") (pinfunction "3_3") (pintype "passive"))
      (node (ref "PS2") (pin "3") (pinfunction "-VOUT_3") (pintype "output"))
      (node (ref "X10") (pin "5") (pinfunction "GND2_5") (pintype "power_in"))
    )
    (net (code "26") (name "/ISO-GND-3") (class "Default")
      (node (ref "C15") (pin "2") (pinfunction "2_2") (pintype "passive"))
      (node (ref "JP16") (pin "3") (pinfunction "3_3") (pintype "passive"))
      (node (ref "PS3") (pin "3") (pinfunction "-VOUT_3") (pintype "output"))
      (node (ref "X12") (pin "5") (pinfunction "GND2_5") (pintype "power_in"))
    )
    (net (code "27") (name "/ISO-GND-4") (class "Default")
      (node (ref "C17") (pin "2") (pinfunction "2_2") (pintype "passive"))
      (node (ref "JP18") (pin "3") (pinfunction "3_3") (pintype "passive"))
      (node (ref "PS4") (pin "3") (pinfunction "-VOUT_3") (pintype "output"))
      (node (ref "X15") (pin "5") (pinfunction "GND2_5") (pintype "power_in"))
    )
    (net (code "28") (name "/LED1") (class "Default")
      (node (ref "JP4") (pin "2") (pinfunction "2_2") (pintype "passive"))
      (node (ref "R7") (pin "1") (pinfunction "1_1") (pintype "passive"))
      (node (ref "U1") (pin "25") (pinfunction "GPA4_25") (pintype "bidirectional"))
    )
    (net (code "29") (name "/LED2") (class "Default")
      (node (ref "JP4") (pin "4") (pinfunction "4_4") (pintype "passive"))
      (node (ref "R7") (pin "2") (pinfunction "1_2") (pintype "passive"))
      (node (ref "U1") (pin "26") (pinfunction "GPA5_26") (pintype "bidirectional"))
    )
    (net (code "30") (name "/LED3") (class "Default")
      (node (ref "JP4") (pin "6") (pinfunction "6_6") (pintype "passive"))
      (node (ref "R7") (pin "3") (pinfunction "1_3") (pintype "passive"))
      (node (ref "U1") (pin "27") (pinfunction "GPA6_27") (pintype "bidirectional"))
    )
    (net (code "31") (name "/LED4") (class "Default")
      (node (ref "JP4") (pin "8") (pinfunction "8_8") (pintype "passive"))
      (node (ref "R7") (pin "4") (pinfunction "1_4") (pintype "passive"))
      (node (ref "U1") (pin "28") (pinfunction "GPA7_28") (pintype "bidirectional"))
    )
    (net (code "32") (name "/SCL") (class "Default")
      (node (ref "J2") (pin "3") (pinfunction "3_3") (pintype "passive"))
      (node (ref "J3") (pin "3") (pinfunction "3_3") (pintype "passive"))
      (node (ref "J4") (pin "4") (pinfunction "4_4") (pintype "passive"))
      (node (ref "J5") (pin "4") (pinfunction "4_4") (pintype "passive"))
      (node (ref "J6") (pin "4") (pinfunction "4_4") (pintype "passive"))
      (node (ref "J7") (pin "4") (pinfunction "4_4") (pintype "passive"))
      (node (ref "JP11") (pin "5") (pinfunction "5_5") (pintype "passive"))
      (node (ref "JP5") (pin "1") (pinfunction "1_1") (pintype "passive"))
      (node (ref "JP7") (pin "1") (pinfunction "1_1") (pintype "passive"))
      (node (ref "JP9") (pin "1") (pinfunction "1_1") (pintype "passive"))
      (node (ref "R12") (pin "3") (pinfunction "1_3") (pintype "passive"))
      (node (ref "R13") (pin "3") (pinfunction "1_3") (pintype "passive"))
      (node (ref "R17") (pin "3") (pinfunction "1_3") (pintype "passive"))
      (node (ref "R20") (pin "3") (pinfunction "1_3") (pintype "passive"))
      (node (ref "U1") (pin "12") (pinfunction "SCK_12") (pintype "input"))
      (node (ref "X10") (pin "3") (pinfunction "SCL1_3") (pintype "bidirectional"))
      (node (ref "X12") (pin "3") (pinfunction "SCL1_3") (pintype "bidirectional"))
      (node (ref "X13") (pin "8") (pinfunction "8_8") (pintype "passive"))
      (node (ref "X15") (pin "3") (pinfunction "SCL1_3") (pintype "bidirectional"))
      (node (ref "X16") (pin "8") (pinfunction "8_8") (pintype "passive"))
      (node (ref "X3") (pin "1") (pinfunction "S_1") (pintype "passive"))
      (node (ref "X8") (pin "3") (pinfunction "SCL1_3") (pintype "bidirectional"))
      (node (ref "X9") (pin "8") (pinfunction "8_8") (pintype "passive"))
    )
    (net (code "33") (name "/SCL2") (class "Default")
      (node (ref "JP12") (pin "1") (pinfunction "1_1") (pintype "passive"))
      (node (ref "R14") (pin "3") (pinfunction "1_3") (pintype "passive"))
      (node (ref "X8") (pin "6") (pinfunction "SCL2_6") (pintype "bidirectional"))
    )
    (net (code "34") (name "/SCL3") (class "Default")
      (node (ref "JP14") (pin "1") (pinfunction "1_1") (pintype "passive"))
      (node (ref "R16") (pin "3") (pinfunction "1_3") (pintype "passive"))
      (node (ref "X10") (pin "6") (pinfunction "SCL2_6") (pintype "bidirectional"))
    )
    (net (code "35") (name "/SCL4") (class "Default")
      (node (ref "JP16") (pin "1") (pinfunction "1_1") (pintype "passive"))
      (node (ref "R18") (pin "3") (pinfunction "1_3") (pintype "passive"))
      (node (ref "X12") (pin "6") (pinfunction "SCL2_6") (pintype "bidirectional"))
    )
    (net (code "36") (name "/SCL5") (class "Default")
      (node (ref "JP18") (pin "1") (pinfunction "1_1") (pintype "passive"))
      (node (ref "R21") (pin "3") (pinfunction "1_3") (pintype "passive"))
      (node (ref "X15") (pin "6") (pinfunction "SCL2_6") (pintype "bidirectional"))
    )
    (net (code "37") (name "/SDA") (class "Default")
      (node (ref "J2") (pin "4") (pinfunction "4_4") (pintype "passive"))
      (node (ref "J3") (pin "4") (pinfunction "4_4") (pintype "passive"))
      (node (ref "J4") (pin "3") (pinfunction "3_3") (pintype "passive"))
      (node (ref "J5") (pin "3") (pinfunction "3_3") (pintype "passive"))
      (node (ref "J6") (pin "3") (pinfunction "3_3") (pintype "passive"))
      (node (ref "J7") (pin "3") (pinfunction "3_3") (pintype "passive"))
      (node (ref "JP11") (pin "3") (pinfunction "3_3") (pintype "passive"))
      (node (ref "JP5") (pin "2") (pinfunction "2_2") (pintype "passive"))
      (node (ref "JP7") (pin "2") (pinfunction "2_2") (pintype "passive"))
      (node (ref "JP9") (pin "2") (pinfunction "2_2") (pintype "passive"))
      (node (ref "R12") (pin "2") (pinfunction "1_2") (pintype "passive"))
      (node (ref "R13") (pin "2") (pinfunction "1_2") (pintype "passive"))
      (node (ref "R17") (pin "2") (pinfunction "1_2") (pintype "passive"))
      (node (ref "R20") (pin "2") (pinfunction "1_2") (pintype "passive"))
      (node (ref "U1") (pin "13") (pinfunction "SDA_13") (pintype "bidirectional"))
      (node (ref "X10") (pin "2") (pinfunction "SDA1_2") (pintype "bidirectional"))
      (node (ref "X12") (pin "2") (pinfunction "SDA1_2") (pintype "bidirectional"))
      (node (ref "X13") (pin "6") (pinfunction "6_6") (pintype "passive"))
      (node (ref "X15") (pin "2") (pinfunction "SDA1_2") (pintype "bidirectional"))
      (node (ref "X16") (pin "6") (pinfunction "6_6") (pintype "passive"))
      (node (ref "X3") (pin "2") (pinfunction "S_2") (pintype "passive"))
      (node (ref "X8") (pin "2") (pinfunction "SDA1_2") (pintype "bidirectional"))
      (node (ref "X9") (pin "6") (pinfunction "6_6") (pintype "passive"))
    )
    (net (code "38") (name "/SDA2") (class "Default")
      (node (ref "JP12") (pin "2") (pinfunction "2_2") (pintype "passive"))
      (node (ref "R14") (pin "2") (pinfunction "1_2") (pintype "passive"))
      (node (ref "X8") (pin "7") (pinfunction "SDA2_7") (pintype "bidirectional"))
    )
    (net (code "39") (name "/SDA3") (class "Default")
      (node (ref "JP14") (pin "2") (pinfunction "2_2") (pintype "passive"))
      (node (ref "R16") (pin "2") (pinfunction "1_2") (pintype "passive"))
      (node (ref "X10") (pin "7") (pinfunction "SDA2_7") (pintype "bidirectional"))
    )
    (net (code "40") (name "/SDA4") (class "Default")
      (node (ref "JP16") (pin "2") (pinfunction "2_2") (pintype "passive"))
      (node (ref "R18") (pin "2") (pinfunction "1_2") (pintype "passive"))
      (node (ref "X12") (pin "7") (pinfunction "SDA2_7") (pintype "bidirectional"))
    )
    (net (code "41") (name "/SDA5") (class "Default")
      (node (ref "JP18") (pin "2") (pinfunction "2_2") (pintype "passive"))
      (node (ref "R21") (pin "2") (pinfunction "1_2") (pintype "passive"))
      (node (ref "X15") (pin "7") (pinfunction "SDA2_7") (pintype "bidirectional"))
    )
    (net (code "42") (name "12V") (class "Default")
      (node (ref "J8") (pin "PWR") (pinfunction "PWR_PWR") (pintype "bidirectional"))
    )
    (net (code "43") (name "GND") (class "Default")
      (node (ref "C1") (pin "-") (pinfunction "-_-") (pintype "passive"))
      (node (ref "C10") (pin "2") (pinfunction "2_2") (pintype "passive"))
      (node (ref "C12") (pin "2") (pinfunction "2_2") (pintype "passive"))
      (node (ref "C14") (pin "2") (pinfunction "2_2") (pintype "passive"))
      (node (ref "C16") (pin "2") (pinfunction "2_2") (pintype "passive"))
      (node (ref "C1A1") (pin "-") (pinfunction "-_-") (pintype "passive"))
      (node (ref "C1A2") (pin "-") (pinfunction "-_-") (pintype "passive"))
      (node (ref "C1B1") (pin "-") (pinfunction "-_-") (pintype "passive"))
      (node (ref "C1B2") (pin "-") (pinfunction "-_-") (pintype "passive"))
      (node (ref "C2") (pin "1") (pinfunction "1_1") (pintype "passive"))
      (node (ref "C3") (pin "-") (pinfunction "-_-") (pintype "passive"))
      (node (ref "C4") (pin "-") (pinfunction "-_-") (pintype "passive"))
      (node (ref "C5") (pin "-") (pinfunction "-_-") (pintype "passive"))
      (node (ref "C6") (pin "1") (pinfunction "1_1") (pintype "passive"))
      (node (ref "C7") (pin "-") (pinfunction "-_-") (pintype "passive"))
      (node (ref "C8") (pin "-") (pinfunction "-_-") (pintype "passive"))
      (node (ref "C9") (pin "-") (pinfunction "-_-") (pintype "passive"))
      (node (ref "D10") (pin "A") (pinfunction "A_A") (pintype "passive"))
      (node (ref "D17") (pin "A") (pinfunction "A_A") (pintype "passive"))
      (node (ref "D18") (pin "A") (pinfunction "A_A") (pintype "passive"))
      (node (ref "D19") (pin "A") (pinfunction "A_A") (pintype "passive"))
      (node (ref "D20") (pin "A") (pinfunction "A_A") (pintype "passive"))
      (node (ref "D22") (pin "A") (pinfunction "A_A") (pintype "passive"))
      (node (ref "D24") (pin "A") (pinfunction "A_A") (pintype "passive"))
      (node (ref "D26") (pin "A") (pinfunction "A_A") (pintype "passive"))
      (node (ref "D28") (pin "A") (pinfunction "A_A") (pintype "passive"))
      (node (ref "D4") (pin "A") (pinfunction "A_A") (pintype "passive"))
      (node (ref "D6") (pin "A") (pinfunction "A_A") (pintype "passive"))
      (node (ref "D8") (pin "A") (pinfunction "A_A") (pintype "passive"))
      (node (ref "IC2") (pin "8") (pinfunction "GND_8") (pintype "power_in"))
      (node (ref "IC4") (pin "8") (pinfunction "GND_8") (pintype "power_in"))
      (node (ref "IC5") (pin "8") (pinfunction "GND_8") (pintype "power_in"))
      (node (ref "J2") (pin "2") (pinfunction "2_2") (pintype "power_in"))
      (node (ref "J3") (pin "1") (pinfunction "1_1") (pintype "power_in"))
      (node (ref "J4") (pin "1") (pinfunction "1_1") (pintype "power_in"))
      (node (ref "J5") (pin "1") (pinfunction "1_1") (pintype "power_in"))
      (node (ref "J6") (pin "1") (pinfunction "1_1") (pintype "power_in"))
      (node (ref "J7") (pin "1") (pinfunction "1_1") (pintype "power_in"))
      (node (ref "J8") (pin "GND") (pinfunction "GND_GND") (pintype "bidirectional"))
      (node (ref "J8") (pin "GNDBREAK") (pinfunction "GNDBREAK_GNDBREAK") (pintype "bidirectional"))
      (node (ref "JP1") (pin "1") (pinfunction "1_1") (pintype "passive"))
      (node (ref "JP11") (pin "14") (pinfunction "14_14") (pintype "passive"))
      (node (ref "JP11") (pin "6") (pinfunction "6_6") (pintype "passive"))
      (node (ref "JP11") (pin "9") (pinfunction "9_9") (pintype "passive"))
      (node (ref "JP2") (pin "1") (pinfunction "1_1") (pintype "passive"))
      (node (ref "JP3") (pin "1") (pinfunction "1_1") (pintype "passive"))
      (node (ref "JP5") (pin "3") (pinfunction "3_3") (pintype "passive"))
      (node (ref "JP7") (pin "3") (pinfunction "3_3") (pintype "passive"))
      (node (ref "JP9") (pin "3") (pinfunction "3_3") (pintype "passive"))
      (node (ref "LED1") (pin "C") (pinfunction "C_C") (pintype "passive"))
      (node (ref "LED10") (pin "C") (pinfunction "C_C") (pintype "passive"))
      (node (ref "LED11") (pin "C") (pinfunction "C_C") (pintype "passive"))
      (node (ref "LED12") (pin "C") (pinfunction "C_C") (pintype "passive"))
      (node (ref "LED13") (pin "C") (pinfunction "C_C") (pintype "passive"))
      (node (ref "LED14") (pin "C") (pinfunction "C_C") (pintype "passive"))
      (node (ref "LED15") (pin "C") (pinfunction "C_C") (pintype "passive"))
      (node (ref "LED16") (pin "C") (pinfunction "C_C") (pintype "passive"))
      (node (ref "LED2") (pin "C") (pinfunction "C_C") (pintype "passive"))
      (node (ref "LED3") (pin "C") (pinfunction "C_C") (pintype "passive"))
      (node (ref "LED4") (pin "C") (pinfunction "C_C") (pintype "passive"))
      (node (ref "LED5") (pin "C") (pinfunction "C_C") (pintype "passive"))
      (node (ref "LED6") (pin "C") (pinfunction "C_C") (pintype "passive"))
      (node (ref "LED7") (pin "C") (pinfunction "C_C") (pintype "passive"))
      (node (ref "LED8") (pin "C") (pinfunction "C_C") (pintype "passive"))
      (node (ref "LED9") (pin "C") (pinfunction "C_C") (pintype "passive"))
      (node (ref "PS1") (pin "1") (pinfunction "-VIN_1") (pintype "input"))
      (node (ref "PS2") (pin "1") (pinfunction "-VIN_1") (pintype "input"))
      (node (ref "PS3") (pin "1") (pinfunction "-VIN_1") (pintype "input"))
      (node (ref "PS4") (pin "1") (pinfunction "-VIN_1") (pintype "input"))
      (node (ref "R1") (pin "1") (pinfunction "1_1") (pintype "passive"))
      (node (ref "R10") (pin "1") (pinfunction "1_1") (pintype "passive"))
      (node (ref "R11") (pin "1") (pinfunction "1_1") (pintype "passive"))
      (node (ref "R2A1") (pin "1") (pinfunction "1_1") (pintype "passive"))
      (node (ref "R2A2") (pin "1") (pinfunction "1_1") (pintype "passive"))
      (node (ref "R2B1") (pin "2") (pinfunction "2_2") (pintype "passive"))
      (node (ref "R2B2") (pin "2") (pinfunction "2_2") (pintype "passive"))
      (node (ref "R4") (pin "1") (pinfunction "1_1") (pintype "passive"))
      (node (ref "R5") (pin "1") (pinfunction "1_1") (pintype "passive"))
      (node (ref "R5A1") (pin "2") (pinfunction "2_2") (pintype "passive"))
      (node (ref "R5A2") (pin "2") (pinfunction "2_2") (pintype "passive"))
      (node (ref "R5B1") (pin "2") (pinfunction "2_2") (pintype "passive"))
      (node (ref "R5B2") (pin "2") (pinfunction "2_2") (pintype "passive"))
      (node (ref "R6") (pin "1") (pinfunction "1_1") (pintype "passive"))
      (node (ref "R8") (pin "1") (pinfunction "1_1") (pintype "passive"))
      (node (ref "R9") (pin "1") (pinfunction "1_1") (pintype "passive"))
      (node (ref "U1") (pin "10") (pinfunction "VSS_10") (pintype "power_in"))
      (node (ref "U2") (pin "4") (pinfunction "P$V-_4") (pintype "bidirectional"))
      (node (ref "U3") (pin "4") (pinfunction "P$V-_4") (pintype "bidirectional"))
      (node (ref "X10") (pin "4") (pinfunction "GND1_4") (pintype "power_in"))
      (node (ref "X12") (pin "4") (pinfunction "GND1_4") (pintype "power_in"))
      (node (ref "X13") (pin "2") (pinfunction "2_2") (pintype "passive"))
      (node (ref "X15") (pin "4") (pinfunction "GND1_4") (pintype "power_in"))
      (node (ref "X16") (pin "2") (pinfunction "2_2") (pintype "passive"))
      (node (ref "X4") (pin "2") (pinfunction "S_2") (pintype "passive"))
      (node (ref "X5") (pin "2") (pinfunction "S_2") (pintype "passive"))
      (node (ref "X6") (pin "2") (pinfunction "S_2") (pintype "passive"))
      (node (ref "X7") (pin "2") (pinfunction "S_2") (pintype "passive"))
      (node (ref "X8") (pin "4") (pinfunction "GND1_4") (pintype "power_in"))
      (node (ref "X9") (pin "2") (pinfunction "2_2") (pintype "passive"))
    )
    (net (code "44") (name "Net-(C1A1-Pad+)") (class "Default")
      (node (ref "C1A1") (pin "+") (pinfunction "+_+") (pintype "passive"))
      (node (ref "R1A1") (pin "1") (pinfunction "1_1") (pintype "passive"))
      (node (ref "R4A2") (pin "1") (pinfunction "1_1") (pintype "passive"))
    )
    (net (code "45") (name "Net-(C1A2-Pad+)") (class "Default")
      (node (ref "C1A2") (pin "+") (pinfunction "+_+") (pintype "passive"))
      (node (ref "R1A2") (pin "1") (pinfunction "1_1") (pintype "passive"))
      (node (ref "R4A1") (pin "1") (pinfunction "1_1") (pintype "passive"))
    )
    (net (code "46") (name "Net-(C1B1-Pad+)") (class "Default")
      (node (ref "C1B1") (pin "+") (pinfunction "+_+") (pintype "passive"))
      (node (ref "R1B1") (pin "2") (pinfunction "2_2") (pintype "passive"))
      (node (ref "R4B1") (pin "1") (pinfunction "1_1") (pintype "passive"))
    )
    (net (code "47") (name "Net-(C1B2-Pad+)") (class "Default")
      (node (ref "C1B2") (pin "+") (pinfunction "+_+") (pintype "passive"))
      (node (ref "R1B2") (pin "2") (pinfunction "2_2") (pintype "passive"))
      (node (ref "R4B2") (pin "1") (pinfunction "1_1") (pintype "passive"))
    )
    (net (code "48") (name "Net-(IC1-ADJ)") (class "Default")
      (node (ref "C4") (pin "+") (pinfunction "+_+") (pintype "passive"))
      (node (ref "D1") (pin "A") (pinfunction "A_A") (pintype "passive"))
      (node (ref "IC1") (pin "1") (pinfunction "ADJ_1") (pintype "input"))
      (node (ref "R2") (pin "1") (pinfunction "1_1") (pintype "passive"))
      (node (ref "R4") (pin "2") (pinfunction "2_2") (pintype "passive"))
    )
    (net (code "49") (name "Net-(IC2-OUT1)") (class "Default")
      (node (ref "D3") (pin "A") (pinfunction "A_A") (pintype "passive"))
      (node (ref "D4") (pin "C") (pinfunction "C_C") (pintype "passive"))
      (node (ref "IC2") (pin "2") (pinfunction "OUT1_2") (pintype "output"))
      (node (ref "R15") (pin "1") (pinfunction "1_1") (pintype "passive"))
      (node (ref "X9") (pin "1") (pinfunction "1_1") (pintype "passive"))
    )
    (net (code "50") (name "Net-(IC2-OUT2)") (class "Default")
      (node (ref "D5") (pin "A") (pinfunction "A_A") (pintype "passive"))
      (node (ref "D6") (pin "C") (pinfunction "C_C") (pintype "passive"))
      (node (ref "IC2") (pin "3") (pinfunction "OUT2_3") (pintype "output"))
      (node (ref "R15") (pin "2") (pinfunction "1_2") (pintype "passive"))
      (node (ref "X9") (pin "3") (pinfunction "3_3") (pintype "passive"))
    )
    (net (code "51") (name "Net-(IC2-OUT3)") (class "Default")
      (node (ref "D7") (pin "A") (pinfunction "A_A") (pintype "passive"))
      (node (ref "D8") (pin "C") (pinfunction "C_C") (pintype "passive"))
      (node (ref "IC2") (pin "13") (pinfunction "OUT3_13") (pintype "output"))
      (node (ref "R15") (pin "3") (pinfunction "1_3") (pintype "passive"))
      (node (ref "X9") (pin "5") (pinfunction "5_5") (pintype "passive"))
    )
    (net (code "52") (name "Net-(IC2-OUT4)") (class "Default")
      (node (ref "D10") (pin "C") (pinfunction "C_C") (pintype "passive"))
      (node (ref "D9") (pin "A") (pinfunction "A_A") (pintype "passive"))
      (node (ref "IC2") (pin "14") (pinfunction "OUT4_14") (pintype "output"))
      (node (ref "R15") (pin "4") (pinfunction "1_4") (pintype "passive"))
      (node (ref "X9") (pin "7") (pinfunction "7_7") (pintype "passive"))
    )
    (net (code "53") (name "Net-(IC2-SEN_A)") (class "Default")
      (node (ref "IC2") (pin "1") (pinfunction "SEN_A_1") (pintype "input"))
      (node (ref "R1") (pin "2") (pinfunction "2_2") (pintype "passive"))
    )
    (net (code "54") (name "Net-(IC2-SEN_B)") (class "Default")
      (node (ref "IC2") (pin "15") (pinfunction "SEN_B_15") (pintype "input"))
      (node (ref "R6") (pin "2") (pinfunction "2_2") (pintype "passive"))
    )
    (net (code "55") (name "Net-(IC3-ADJ)") (class "Default")
      (node (ref "C8") (pin "+") (pinfunction "+_+") (pintype "passive"))
      (node (ref "D11") (pin "A") (pinfunction "A_A") (pintype "passive"))
      (node (ref "IC3") (pin "1") (pinfunction "ADJ_1") (pintype "input"))
      (node (ref "R3") (pin "1") (pinfunction "1_1") (pintype "passive"))
      (node (ref "R5") (pin "2") (pinfunction "2_2") (pintype "passive"))
    )
    (net (code "56") (name "Net-(IC4-OUT1)") (class "Default")
      (node (ref "D13") (pin "A") (pinfunction "A_A") (pintype "passive"))
      (node (ref "D17") (pin "C") (pinfunction "C_C") (pintype "passive"))
      (node (ref "IC4") (pin "2") (pinfunction "OUT1_2") (pintype "output"))
      (node (ref "R19") (pin "1") (pinfunction "1_1") (pintype "passive"))
      (node (ref "X13") (pin "1") (pinfunction "1_1") (pintype "passive"))
    )
    (net (code "57") (name "Net-(IC4-OUT2)") (class "Default")
      (node (ref "D14") (pin "A") (pinfunction "A_A") (pintype "passive"))
      (node (ref "D18") (pin "C") (pinfunction "C_C") (pintype "passive"))
      (node (ref "IC4") (pin "3") (pinfunction "OUT2_3") (pintype "output"))
      (node (ref "R19") (pin "2") (pinfunction "1_2") (pintype "passive"))
      (node (ref "X13") (pin "3") (pinfunction "3_3") (pintype "passive"))
    )
    (net (code "58") (name "Net-(IC4-OUT3)") (class "Default")
      (node (ref "D15") (pin "A") (pinfunction "A_A") (pintype "passive"))
      (node (ref "D19") (pin "C") (pinfunction "C_C") (pintype "passive"))
      (node (ref "IC4") (pin "13") (pinfunction "OUT3_13") (pintype "output"))
      (node (ref "R19") (pin "3") (pinfunction "1_3") (pintype "passive"))
      (node (ref "X13") (pin "5") (pinfunction "5_5") (pintype "passive"))
    )
    (net (code "59") (name "Net-(IC4-OUT4)") (class "Default")
      (node (ref "D16") (pin "A") (pinfunction "A_A") (pintype "passive"))
      (node (ref "D20") (pin "C") (pinfunction "C_C") (pintype "passive"))
      (node (ref "IC4") (pin "14") (pinfunction "OUT4_14") (pintype "output"))
      (node (ref "R19") (pin "4") (pinfunction "1_4") (pintype "passive"))
      (node (ref "X13") (pin "7") (pinfunction "7_7") (pintype "passive"))
    )
    (net (code "60") (name "Net-(IC4-SEN_A)") (class "Default")
      (node (ref "IC4") (pin "1") (pinfunction "SEN_A_1") (pintype "input"))
      (node (ref "R9") (pin "2") (pinfunction "2_2") (pintype "passive"))
    )
    (net (code "61") (name "Net-(IC4-SEN_B)") (class "Default")
      (node (ref "IC4") (pin "15") (pinfunction "SEN_B_15") (pintype "input"))
      (node (ref "R8") (pin "2") (pinfunction "2_2") (pintype "passive"))
    )
    (net (code "62") (name "Net-(IC5-OUT1)") (class "Default")
      (node (ref "D21") (pin "A") (pinfunction "A_A") (pintype "passive"))
      (node (ref "D22") (pin "C") (pinfunction "C_C") (pintype "passive"))
      (node (ref "IC5") (pin "2") (pinfunction "OUT1_2") (pintype "output"))
      (node (ref "R22") (pin "1") (pinfunction "1_1") (pintype "passive"))
      (node (ref "X16") (pin "1") (pinfunction "1_1") (pintype "passive"))
    )
    (net (code "63") (name "Net-(IC5-OUT2)") (class "Default")
      (node (ref "D23") (pin "A") (pinfunction "A_A") (pintype "passive"))
      (node (ref "D24") (pin "C") (pinfunction "C_C") (pintype "passive"))
      (node (ref "IC5") (pin "3") (pinfunction "OUT2_3") (pintype "output"))
      (node (ref "R22") (pin "2") (pinfunction "1_2") (pintype "passive"))
      (node (ref "X16") (pin "3") (pinfunction "3_3") (pintype "passive"))
    )
    (net (code "64") (name "Net-(IC5-OUT3)") (class "Default")
      (node (ref "D25") (pin "A") (pinfunction "A_A") (pintype "passive"))
      (node (ref "D26") (pin "C") (pinfunction "C_C") (pintype "passive"))
      (node (ref "IC5") (pin "13") (pinfunction "OUT3_13") (pintype "output"))
      (node (ref "R22") (pin "3") (pinfunction "1_3") (pintype "passive"))
      (node (ref "X16") (pin "5") (pinfunction "5_5") (pintype "passive"))
    )
    (net (code "65") (name "Net-(IC5-OUT4)") (class "Default")
      (node (ref "D27") (pin "A") (pinfunction "A_A") (pintype "passive"))
      (node (ref "D28") (pin "C") (pinfunction "C_C") (pintype "passive"))
      (node (ref "IC5") (pin "14") (pinfunction "OUT4_14") (pintype "output"))
      (node (ref "R22") (pin "4") (pinfunction "1_4") (pintype "passive"))
      (node (ref "X16") (pin "7") (pinfunction "7_7") (pintype "passive"))
    )
    (net (code "66") (name "Net-(IC5-SEN_A)") (class "Default")
      (node (ref "IC5") (pin "1") (pinfunction "SEN_A_1") (pintype "input"))
      (node (ref "R11") (pin "2") (pinfunction "2_2") (pintype "passive"))
    )
    (net (code "67") (name "Net-(IC5-SEN_B)") (class "Default")
      (node (ref "IC5") (pin "15") (pinfunction "SEN_B_15") (pintype "input"))
      (node (ref "R10") (pin "2") (pinfunction "2_2") (pintype "passive"))
    )
    (net (code "68") (name "Net-(JP13-Pad2)") (class "Default")
      (node (ref "JP13") (pin "2") (pinfunction "2_2") (pintype "passive"))
      (node (ref "X18") (pin "1") (pinfunction "1_1") (pintype "passive"))
    )
    (net (code "69") (name "Net-(JP13-Pad3)") (class "Default")
      (node (ref "JP13") (pin "3") (pinfunction "3_3") (pintype "passive"))
      (node (ref "X18") (pin "2") (pinfunction "2_2") (pintype "passive"))
      (node (ref "X18") (pin "3") (pinfunction "2_3") (pintype "passive"))
      (node (ref "X18") (pin "4") (pinfunction "2_4") (pintype "passive"))
      (node (ref "X18") (pin "5") (pinfunction "2_5") (pintype "passive"))
    )
    (net (code "70") (name "Net-(JP15-Pad2)") (class "Default")
      (node (ref "JP15") (pin "2") (pinfunction "2_2") (pintype "passive"))
      (node (ref "X19") (pin "1") (pinfunction "1_1") (pintype "passive"))
    )
    (net (code "71") (name "Net-(JP15-Pad3)") (class "Default")
      (node (ref "JP15") (pin "3") (pinfunction "3_3") (pintype "passive"))
      (node (ref "X19") (pin "2") (pinfunction "2_2") (pintype "passive"))
      (node (ref "X19") (pin "3") (pinfunction "2_3") (pintype "passive"))
      (node (ref "X19") (pin "4") (pinfunction "2_4") (pintype "passive"))
      (node (ref "X19") (pin "5") (pinfunction "2_5") (pintype "passive"))
    )
    (net (code "72") (name "Net-(JP17-Pad2)") (class "Default")
      (node (ref "JP17") (pin "2") (pinfunction "2_2") (pintype "passive"))
      (node (ref "X20") (pin "1") (pinfunction "1_1") (pintype "passive"))
    )
    (net (code "73") (name "Net-(JP17-Pad3)") (class "Default")
      (node (ref "JP17") (pin "3") (pinfunction "3_3") (pintype "passive"))
      (node (ref "X20") (pin "2") (pinfunction "2_2") (pintype "passive"))
      (node (ref "X20") (pin "3") (pinfunction "2_3") (pintype "passive"))
      (node (ref "X20") (pin "4") (pinfunction "2_4") (pintype "passive"))
      (node (ref "X20") (pin "5") (pinfunction "2_5") (pintype "passive"))
    )
    (net (code "74") (name "Net-(JP19-Pad2)") (class "Default")
      (node (ref "JP19") (pin "2") (pinfunction "2_2") (pintype "passive"))
      (node (ref "X21") (pin "1") (pinfunction "1_1") (pintype "passive"))
    )
    (net (code "75") (name "Net-(JP19-Pad3)") (class "Default")
      (node (ref "JP19") (pin "3") (pinfunction "3_3") (pintype "passive"))
      (node (ref "X21") (pin "2") (pinfunction "2_2") (pintype "passive"))
      (node (ref "X21") (pin "3") (pinfunction "2_3") (pintype "passive"))
      (node (ref "X21") (pin "4") (pinfunction "2_4") (pintype "passive"))
      (node (ref "X21") (pin "5") (pinfunction "2_5") (pintype "passive"))
    )
    (net (code "76") (name "Net-(R3-1A1-CCW)") (class "Default")
      (node (ref "R2A1") (pin "2") (pinfunction "2_2") (pintype "passive"))
      (node (ref "R3-1A1") (pin "1") (pinfunction "CCW_1") (pintype "passive"))
      (node (ref "U2") (pin "6") (pinfunction "-IN_6") (pintype "input"))
    )
    (net (code "77") (name "Net-(R3-1A1-CW)") (class "Default")
      (node (ref "R3-1A1") (pin "2") (pinfunction "WIPER_2") (pintype "passive"))
      (node (ref "R3-1A1") (pin "3") (pinfunction "CW_3") (pintype "passive"))
      (node (ref "R3-2A1") (pin "1") (pinfunction "1_1") (pintype "passive"))
    )
    (net (code "78") (name "Net-(R3-1A2-CCW)") (class "Default")
      (node (ref "R2A2") (pin "2") (pinfunction "2_2") (pintype "passive"))
      (node (ref "R3-1A2") (pin "1") (pinfunction "CCW_1") (pintype "passive"))
      (node (ref "U3") (pin "6") (pinfunction "-IN_6") (pintype "input"))
    )
    (net (code "79") (name "Net-(R3-1A2-CW)") (class "Default")
      (node (ref "R3-1A2") (pin "2") (pinfunction "WIPER_2") (pintype "passive"))
      (node (ref "R3-1A2") (pin "3") (pinfunction "CW_3") (pintype "passive"))
      (node (ref "R3-2A2") (pin "1") (pinfunction "1_1") (pintype "passive"))
    )
    (net (code "80") (name "Net-(R3-1B1-CCW)") (class "Default")
      (node (ref "R2B1") (pin "1") (pinfunction "1_1") (pintype "passive"))
      (node (ref "R3-1B1") (pin "1") (pinfunction "CCW_1") (pintype "passive"))
      (node (ref "U2") (pin "2") (pinfunction "-IN_2") (pintype "input"))
    )
    (net (code "81") (name "Net-(R3-1B1-CW)") (class "Default")
      (node (ref "R3-1B1") (pin "2") (pinfunction "WIPER_2") (pintype "passive"))
      (node (ref "R3-1B1") (pin "3") (pinfunction "CW_3") (pintype "passive"))
      (node (ref "R3-2B1") (pin "1") (pinfunction "1_1") (pintype "passive"))
    )
    (net (code "82") (name "Net-(R3-1B2-CCW)") (class "Default")
      (node (ref "R2B2") (pin "1") (pinfunction "1_1") (pintype "passive"))
      (node (ref "R3-1B2") (pin "1") (pinfunction "CCW_1") (pintype "passive"))
      (node (ref "U3") (pin "2") (pinfunction "-IN_2") (pintype "input"))
    )
    (net (code "83") (name "Net-(R3-1B2-CW)") (class "Default")
      (node (ref "R3-1B2") (pin "2") (pinfunction "WIPER_2") (pintype "passive"))
      (node (ref "R3-1B2") (pin "3") (pinfunction "CW_3") (pintype "passive"))
      (node (ref "R3-2B2") (pin "1") (pinfunction "1_1") (pintype "passive"))
    )
    (net (code "84") (name "Net-(R3-2A1-Pad2)") (class "Default")
      (node (ref "R3-2A1") (pin "2") (pinfunction "2_2") (pintype "passive"))
      (node (ref "R3-3A1") (pin "1") (pinfunction "1_1") (pintype "passive"))
    )
    (net (code "85") (name "Net-(R3-2A2-Pad2)") (class "Default")
      (node (ref "R3-2A2") (pin "2") (pinfunction "2_2") (pintype "passive"))
      (node (ref "R3-3A2") (pin "1") (pinfunction "1_1") (pintype "passive"))
    )
    (net (code "86") (name "Net-(R3-2B1-Pad2)") (class "Default")
      (node (ref "R3-2B1") (pin "2") (pinfunction "2_2") (pintype "passive"))
      (node (ref "R3-3B1") (pin "1") (pinfunction "1_1") (pintype "passive"))
    )
    (net (code "87") (name "Net-(R3-2B2-Pad2)") (class "Default")
      (node (ref "R3-2B2") (pin "2") (pinfunction "2_2") (pintype "passive"))
      (node (ref "R3-3B2") (pin "1") (pinfunction "1_1") (pintype "passive"))
    )
    (net (code "88") (name "Net-(R7A-2)") (class "Default")
      (node (ref "LED1") (pin "A") (pinfunction "A_A") (pintype "passive"))
      (node (ref "R7") (pin "8") (pinfunction "2_8") (pintype "passive"))
    )
    (net (code "89") (name "Net-(R7B-2)") (class "Default")
      (node (ref "LED2") (pin "A") (pinfunction "A_A") (pintype "passive"))
      (node (ref "R7") (pin "7") (pinfunction "2_7") (pintype "passive"))
    )
    (net (code "90") (name "Net-(R7C-2)") (class "Default")
      (node (ref "LED3") (pin "A") (pinfunction "A_A") (pintype "passive"))
      (node (ref "R7") (pin "6") (pinfunction "2_6") (pintype "passive"))
    )
    (net (code "91") (name "Net-(R7D-2)") (class "Default")
      (node (ref "LED4") (pin "A") (pinfunction "A_A") (pintype "passive"))
      (node (ref "R7") (pin "5") (pinfunction "2_5") (pintype "passive"))
    )
    (net (code "92") (name "Net-(R15A-2)") (class "Default")
      (node (ref "LED5") (pin "A") (pinfunction "A_A") (pintype "passive"))
      (node (ref "R15") (pin "8") (pinfunction "2_8") (pintype "passive"))
    )
    (net (code "93") (name "Net-(R15B-2)") (class "Default")
      (node (ref "LED6") (pin "A") (pinfunction "A_A") (pintype "passive"))
      (node (ref "R15") (pin "7") (pinfunction "2_7") (pintype "passive"))
    )
    (net (code "94") (name "Net-(R15C-2)") (class "Default")
      (node (ref "LED7") (pin "A") (pinfunction "A_A") (pintype "passive"))
      (node (ref "R15") (pin "6") (pinfunction "2_6") (pintype "passive"))
    )
    (net (code "95") (name "Net-(R15D-2)") (class "Default")
      (node (ref "LED8") (pin "A") (pinfunction "A_A") (pintype "passive"))
      (node (ref "R15") (pin "5") (pinfunction "2_5") (pintype "passive"))
    )
    (net (code "96") (name "Net-(R19A-2)") (class "Default")
      (node (ref "LED9") (pin "A") (pinfunction "A_A") (pintype "passive"))
      (node (ref "R19") (pin "8") (pinfunction "2_8") (pintype "passive"))
    )
    (net (code "97") (name "Net-(R19B-2)") (class "Default")
      (node (ref "LED10") (pin "A") (pinfunction "A_A") (pintype "passive"))
      (node (ref "R19") (pin "7") (pinfunction "2_7") (pintype "passive"))
    )
    (net (code "98") (name "Net-(R19C-2)") (class "Default")
      (node (ref "LED11") (pin "A") (pinfunction "A_A") (pintype "passive"))
      (node (ref "R19") (pin "6") (pinfunction "2_6") (pintype "passive"))
    )
    (net (code "99") (name "Net-(R19D-2)") (class "Default")
      (node (ref "LED12") (pin "A") (pinfunction "A_A") (pintype "passive"))
      (node (ref "R19") (pin "5") (pinfunction "2_5") (pintype "passive"))
    )
    (net (code "100") (name "Net-(R22A-2)") (class "Default")
      (node (ref "LED13") (pin "A") (pinfunction "A_A") (pintype "passive"))
      (node (ref "R22") (pin "8") (pinfunction "2_8") (pintype "passive"))
    )
    (net (code "101") (name "Net-(R22B-2)") (class "Default")
      (node (ref "LED14") (pin "A") (pinfunction "A_A") (pintype "passive"))
      (node (ref "R22") (pin "7") (pinfunction "2_7") (pintype "passive"))
    )
    (net (code "102") (name "Net-(R22C-2)") (class "Default")
      (node (ref "LED15") (pin "A") (pinfunction "A_A") (pintype "passive"))
      (node (ref "R22") (pin "6") (pinfunction "2_6") (pintype "passive"))
    )
    (net (code "103") (name "Net-(R22D-2)") (class "Default")
      (node (ref "LED16") (pin "A") (pinfunction "A_A") (pintype "passive"))
      (node (ref "R22") (pin "5") (pinfunction "2_5") (pintype "passive"))
    )
    (net (code "104") (name "Net-(U1-A0)") (class "Default")
      (node (ref "JP1") (pin "2") (pinfunction "2_2") (pintype "passive"))
      (node (ref "U1") (pin "15") (pinfunction "A0_15") (pintype "input"))
    )
    (net (code "105") (name "Net-(U1-A1)") (class "Default")
      (node (ref "JP2") (pin "2") (pinfunction "2_2") (pintype "passive"))
      (node (ref "U1") (pin "16") (pinfunction "A1_16") (pintype "input"))
    )
    (net (code "106") (name "Net-(U1-A2)") (class "Default")
      (node (ref "JP3") (pin "2") (pinfunction "2_2") (pintype "passive"))
      (node (ref "U1") (pin "17") (pinfunction "A2_17") (pintype "input"))
    )
    (net (code "107") (name "Net-(U2A-+IN)") (class "Default")
      (node (ref "R4B1") (pin "2") (pinfunction "2_2") (pintype "passive"))
      (node (ref "U2") (pin "3") (pinfunction "+IN_3") (pintype "input"))
    )
    (net (code "108") (name "Net-(U2A-OUT)") (class "Default")
      (node (ref "R3-3B1") (pin "2") (pinfunction "2_2") (pintype "passive"))
      (node (ref "U2") (pin "1") (pinfunction "OUT_1") (pintype "output"))
      (node (ref "X5") (pin "1") (pinfunction "S_1") (pintype "passive"))
    )
    (net (code "109") (name "Net-(U2B-+IN)") (class "Default")
      (node (ref "R4A2") (pin "2") (pinfunction "2_2") (pintype "passive"))
      (node (ref "U2") (pin "5") (pinfunction "+IN_5") (pintype "input"))
    )
    (net (code "110") (name "Net-(U2B-OUT)") (class "Default")
      (node (ref "R3-3A1") (pin "2") (pinfunction "2_2") (pintype "passive"))
      (node (ref "U2") (pin "7") (pinfunction "OUT_7") (pintype "output"))
      (node (ref "X4") (pin "1") (pinfunction "S_1") (pintype "passive"))
    )
    (net (code "111") (name "Net-(U3A-+IN)") (class "Default")
      (node (ref "R4B2") (pin "2") (pinfunction "2_2") (pintype "passive"))
      (node (ref "U3") (pin "3") (pinfunction "+IN_3") (pintype "input"))
    )
    (net (code "112") (name "Net-(U3A-OUT)") (class "Default")
      (node (ref "R3-3B2") (pin "2") (pinfunction "2_2") (pintype "passive"))
      (node (ref "U3") (pin "1") (pinfunction "OUT_1") (pintype "output"))
      (node (ref "X7") (pin "1") (pinfunction "S_1") (pintype "passive"))
    )
    (net (code "113") (name "Net-(U3B-+IN)") (class "Default")
      (node (ref "R4A1") (pin "2") (pinfunction "2_2") (pintype "passive"))
      (node (ref "U3") (pin "5") (pinfunction "+IN_5") (pintype "input"))
    )
    (net (code "114") (name "Net-(U3B-OUT)") (class "Default")
      (node (ref "R3-3A2") (pin "2") (pinfunction "2_2") (pintype "passive"))
      (node (ref "U3") (pin "7") (pinfunction "OUT_7") (pintype "output"))
      (node (ref "X6") (pin "1") (pinfunction "S_1") (pintype "passive"))
    )
    (net (code "115") (name "Net-(X11A-S)") (class "Default")
      (node (ref "JP6") (pin "3") (pinfunction "3_3") (pintype "passive"))
      (node (ref "X11") (pin "1") (pinfunction "S_1") (pintype "passive"))
    )
    (net (code "116") (name "Net-(X11B-S)") (class "Default")
      (node (ref "JP6") (pin "2") (pinfunction "2_2") (pintype "passive"))
      (node (ref "X11") (pin "2") (pinfunction "S_2") (pintype "passive"))
    )
    (net (code "117") (name "Net-(X14A-S)") (class "Default")
      (node (ref "JP8") (pin "3") (pinfunction "3_3") (pintype "passive"))
      (node (ref "X14") (pin "1") (pinfunction "S_1") (pintype "passive"))
    )
    (net (code "118") (name "Net-(X14B-S)") (class "Default")
      (node (ref "JP8") (pin "2") (pinfunction "2_2") (pintype "passive"))
      (node (ref "X14") (pin "2") (pinfunction "S_2") (pintype "passive"))
    )
    (net (code "119") (name "Net-(X17A-S)") (class "Default")
      (node (ref "JP10") (pin "3") (pinfunction "3_3") (pintype "passive"))
      (node (ref "X17") (pin "1") (pinfunction "S_1") (pintype "passive"))
    )
    (net (code "120") (name "Net-(X17B-S)") (class "Default")
      (node (ref "JP10") (pin "2") (pinfunction "2_2") (pintype "passive"))
      (node (ref "X17") (pin "2") (pinfunction "S_2") (pintype "passive"))
    )
    (net (code "121") (name "unconnected-(JP11-Pad1)") (class "Default")
      (node (ref "JP11") (pin "1") (pinfunction "1_1") (pintype "passive"))
    )
    (net (code "122") (name "unconnected-(JP11-Pad2)") (class "Default")
      (node (ref "JP11") (pin "2") (pinfunction "2_2") (pintype "passive"))
    )
    (net (code "123") (name "unconnected-(JP11-Pad4)") (class "Default")
      (node (ref "JP11") (pin "4") (pinfunction "4_4") (pintype "passive"))
    )
    (net (code "124") (name "unconnected-(JP11-Pad8)") (class "Default")
      (node (ref "JP11") (pin "8") (pinfunction "8_8") (pintype "passive"))
    )
    (net (code "125") (name "unconnected-(JP11-Pad10)") (class "Default")
      (node (ref "JP11") (pin "10") (pinfunction "10_10") (pintype "passive"))
    )
    (net (code "126") (name "unconnected-(U1-INTA-Pad20)") (class "Default")
      (node (ref "U1") (pin "20") (pinfunction "INTA_20") (pintype "output"))
    )
    (net (code "127") (name "unconnected-(U1-INTB-Pad19)") (class "Default")
      (node (ref "U1") (pin "19") (pinfunction "INTB_19") (pintype "output"))
    )
  )
)
